# pi-kvm_v1_1.net
KiCad netlist of a schematic drawn in Altium Designer
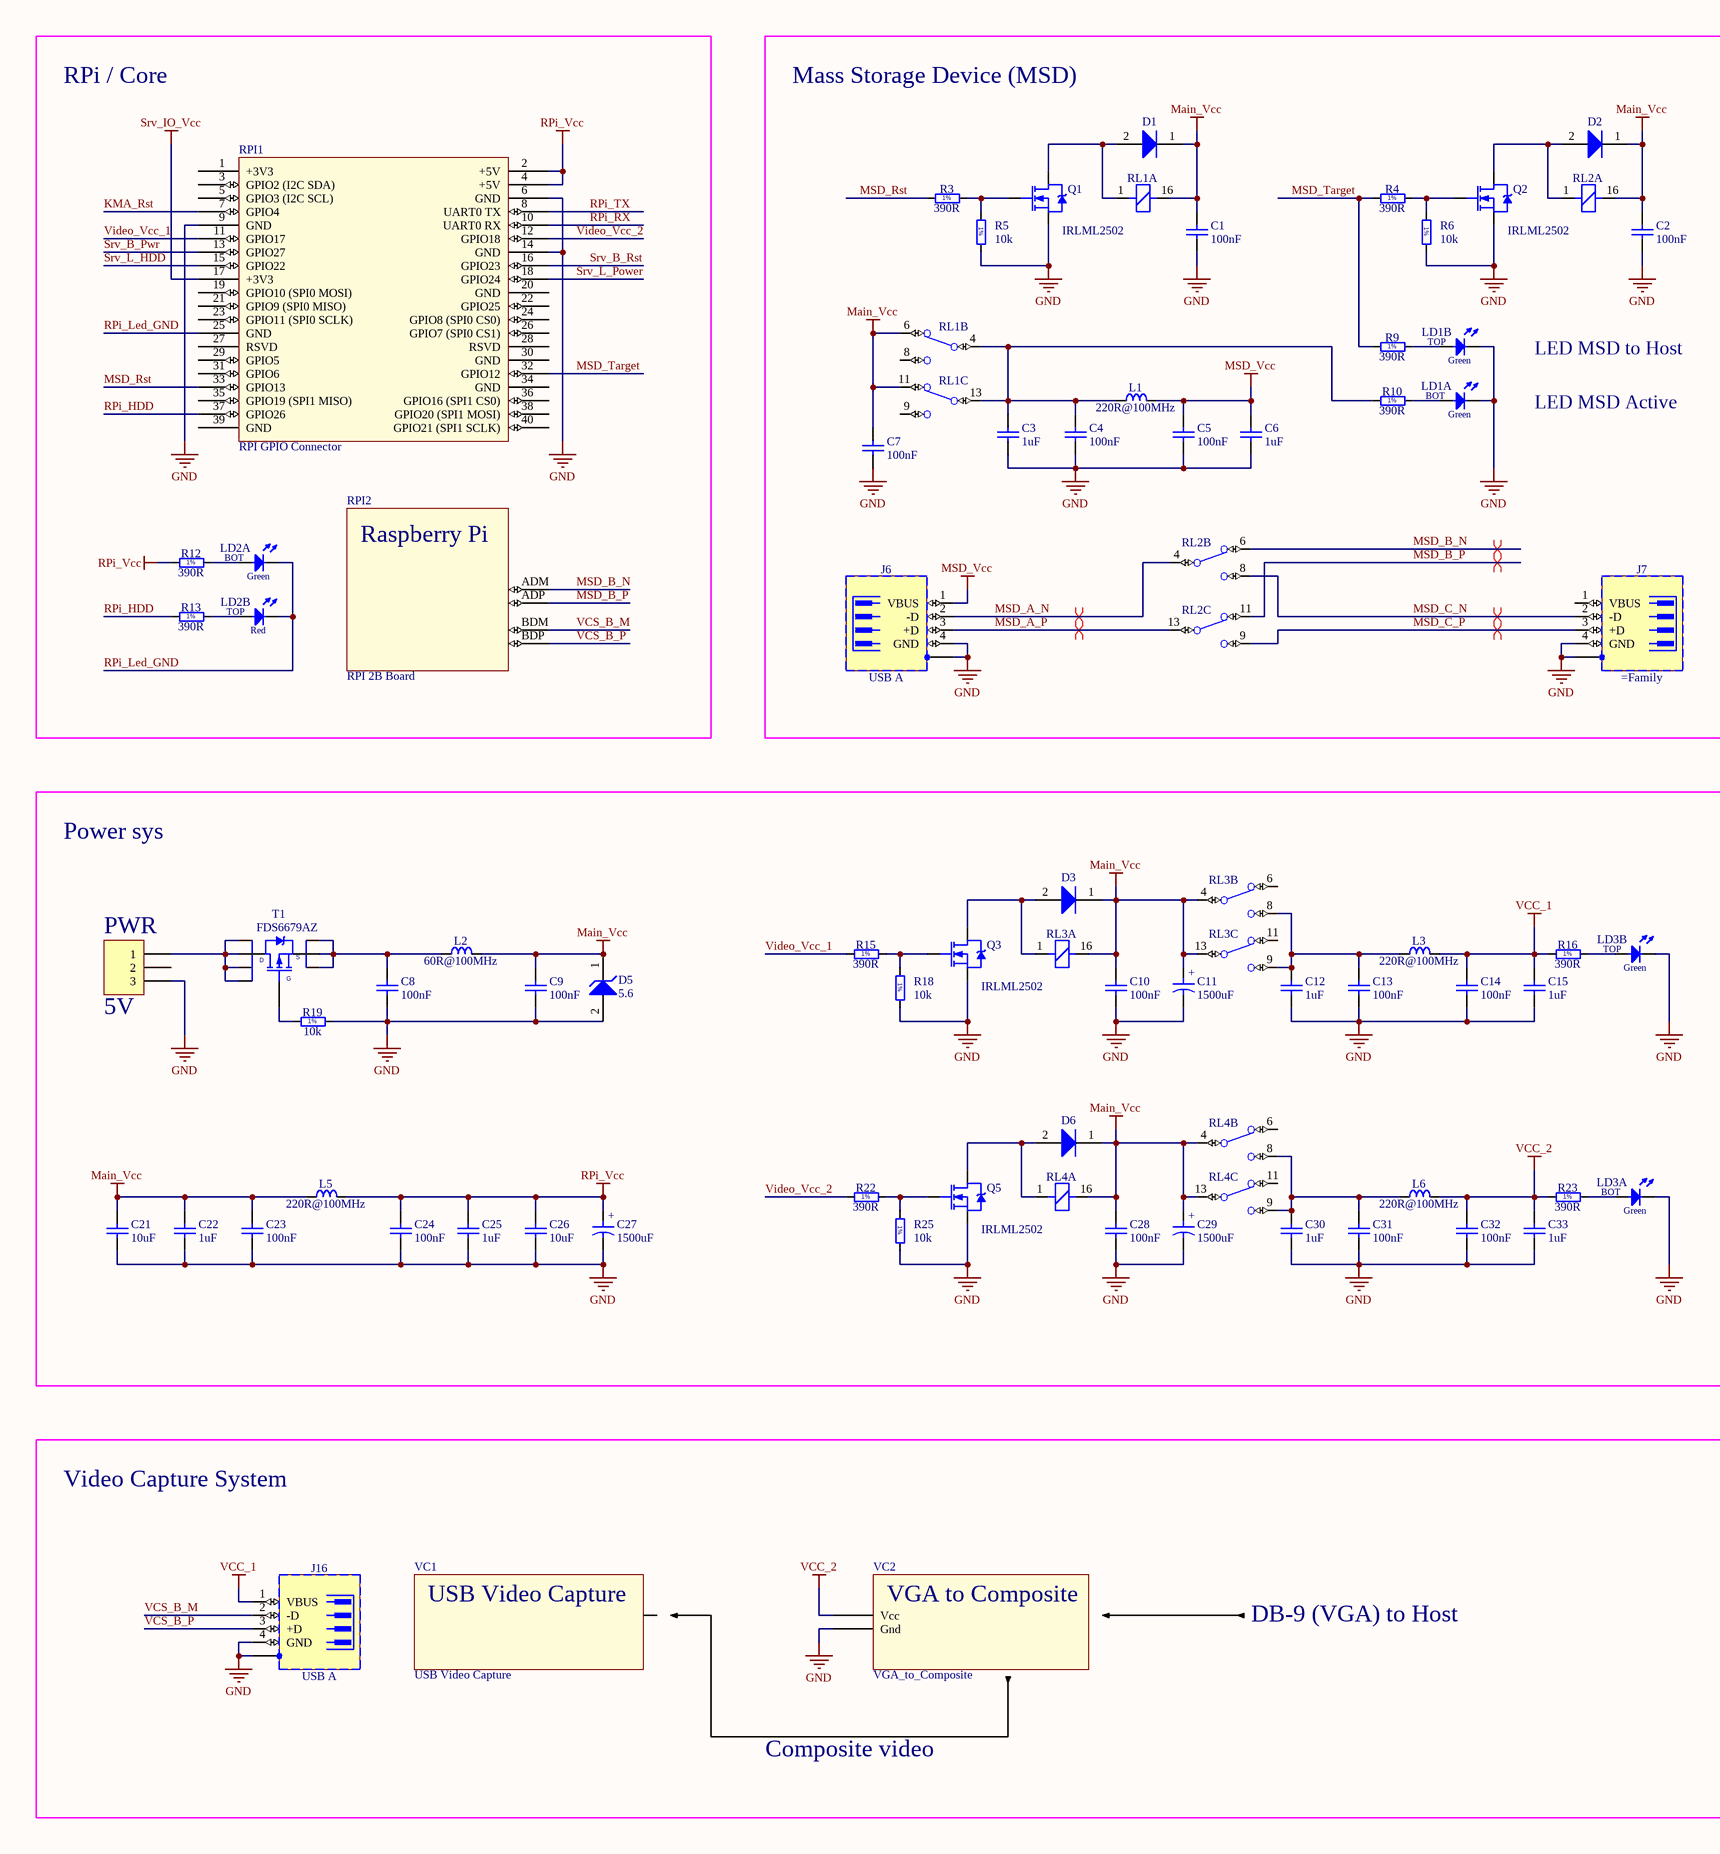
[diagram p0: pi-kvm_v1.1.SchDoc, left]
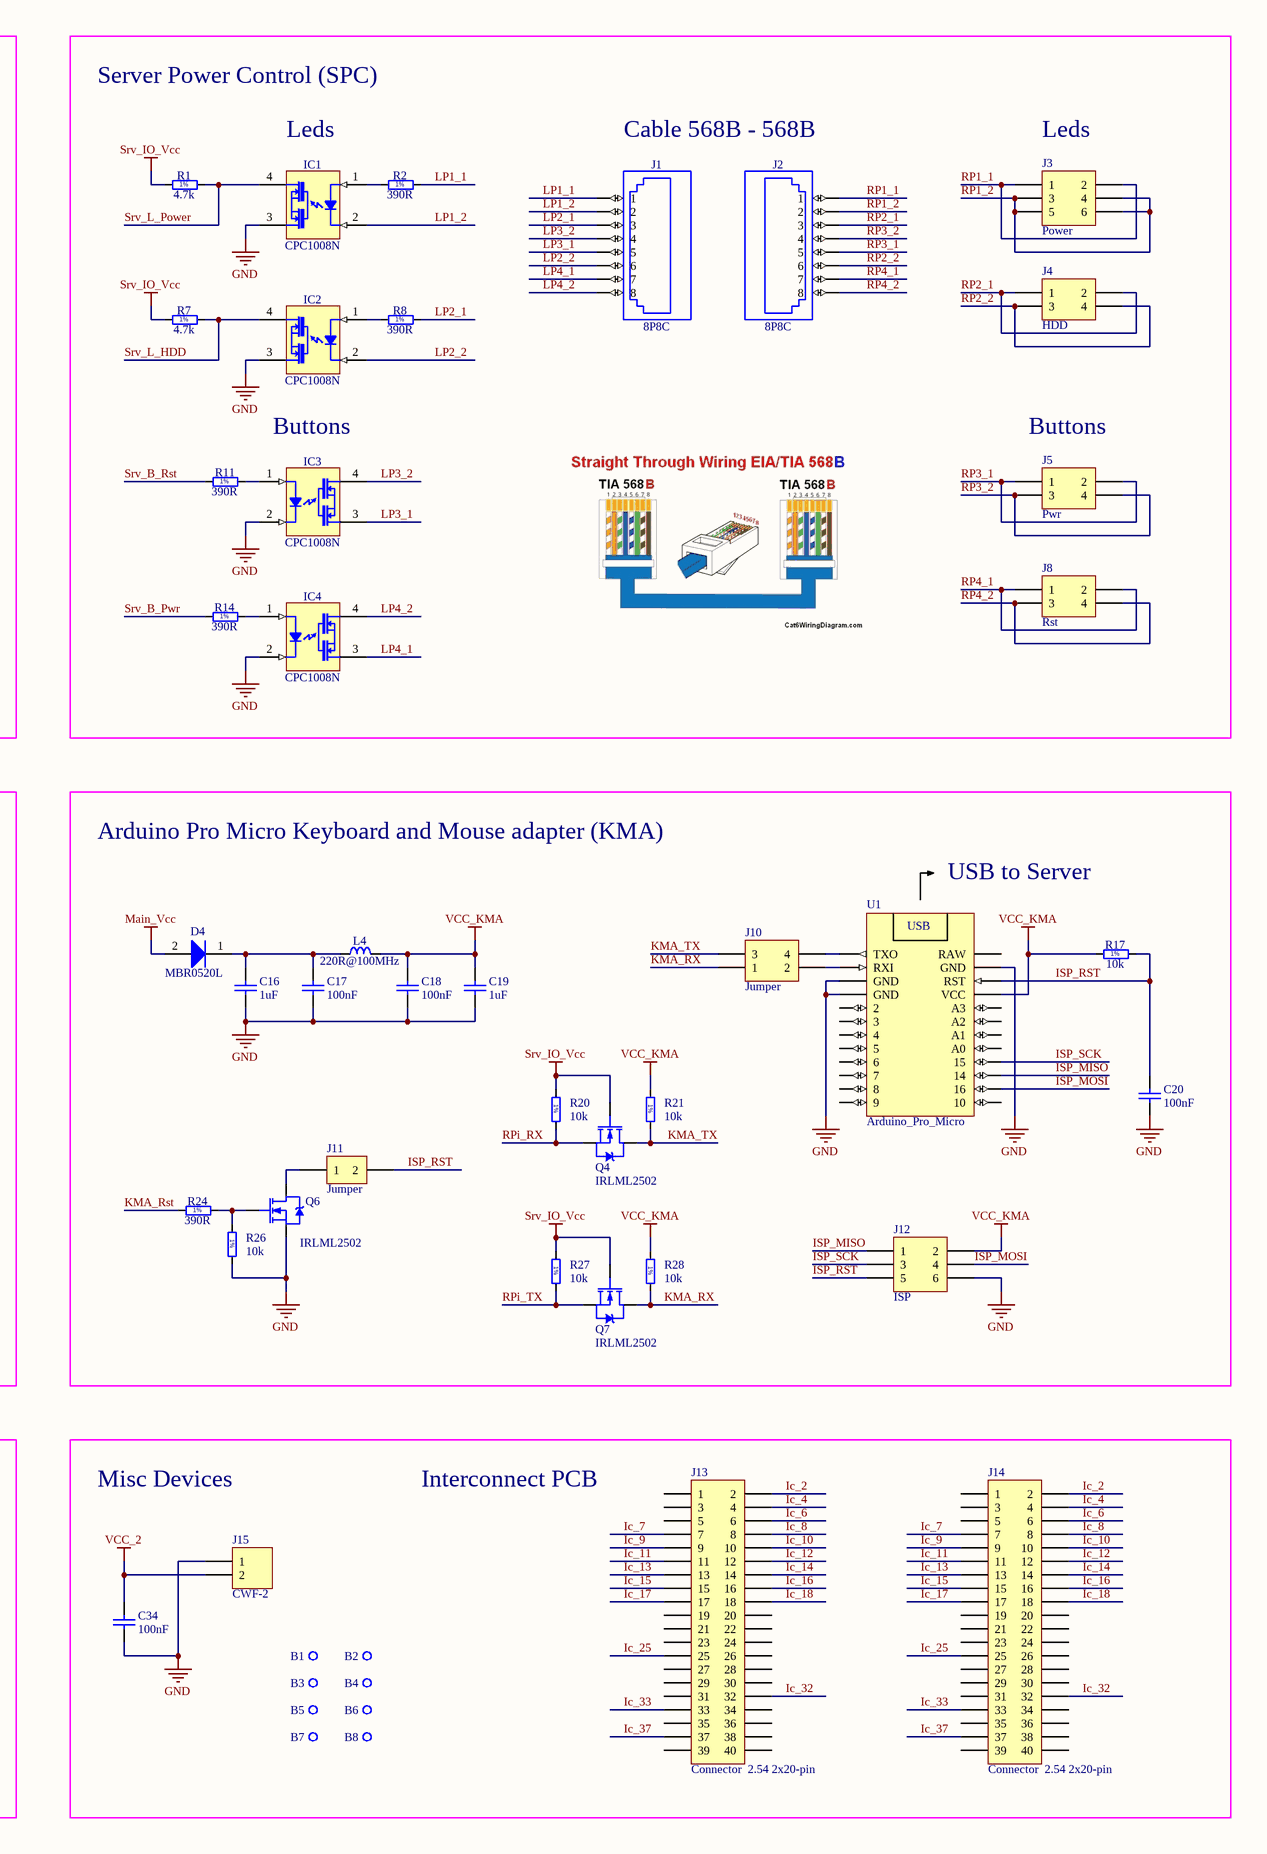
[diagram p1: pi-kvm_v1.1.SchDoc, right]

(export (version "E")
  (design (tool "Eeschema 10.0.6"))
  (components
    (comp (ref "B1")
      (value "~")
      (footprint "awesome_lib_1:MTG300_600_vias")
      (description "PLATED_HOLE3.0_PAD6.0")
      (fields (field (name "MANUFACTURER") "GENERIC"))
      (libsource (lib "awesome_lib_1") (part "PLATED_HOLE3.0_PAD6.0"))
    )
    (comp (ref "B2")
      (value "~")
      (footprint "awesome_lib_1:MTG300_600_vias")
      (description "PLATED_HOLE3.0_PAD6.0")
      (fields (field (name "MANUFACTURER") "GENERIC"))
      (libsource (lib "awesome_lib_1") (part "PLATED_HOLE3.0_PAD6.0"))
    )
    (comp (ref "B3")
      (value "~")
      (footprint "awesome_lib_1:MTG300_600_vias")
      (description "PLATED_HOLE3.0_PAD6.0")
      (fields (field (name "MANUFACTURER") "GENERIC"))
      (libsource (lib "awesome_lib_1") (part "PLATED_HOLE3.0_PAD6.0"))
    )
    (comp (ref "B4")
      (value "~")
      (footprint "awesome_lib_1:MTG300_600_vias")
      (description "PLATED_HOLE3.0_PAD6.0")
      (fields (field (name "MANUFACTURER") "GENERIC"))
      (libsource (lib "awesome_lib_1") (part "PLATED_HOLE3.0_PAD6.0"))
    )
    (comp (ref "B5")
      (value "~")
      (footprint "awesome_lib_1:MTG300_600_vias")
      (description "PLATED_HOLE3.0_PAD6.0")
      (fields (field (name "MANUFACTURER") "GENERIC"))
      (libsource (lib "awesome_lib_1") (part "PLATED_HOLE3.0_PAD6.0"))
    )
    (comp (ref "B6")
      (value "~")
      (footprint "awesome_lib_1:MTG300_600_vias")
      (description "PLATED_HOLE3.0_PAD6.0")
      (fields (field (name "MANUFACTURER") "GENERIC"))
      (libsource (lib "awesome_lib_1") (part "PLATED_HOLE3.0_PAD6.0"))
    )
    (comp (ref "B7")
      (value "~")
      (footprint "awesome_lib_1:MTG300_600_vias")
      (description "PLATED_HOLE3.0_PAD6.0")
      (fields (field (name "MANUFACTURER") "GENERIC"))
      (libsource (lib "awesome_lib_1") (part "PLATED_HOLE3.0_PAD6.0"))
    )
    (comp (ref "B8")
      (value "~")
      (footprint "awesome_lib_1:MTG300_600_vias")
      (description "PLATED_HOLE3.0_PAD6.0")
      (fields (field (name "MANUFACTURER") "GENERIC"))
      (libsource (lib "awesome_lib_1") (part "PLATED_HOLE3.0_PAD6.0"))
    )
    (comp (ref "C1")
      (value "100nF")
      (footprint "awesome_lib_1:CAPC2012X135N")
      (description "C_0805_100nF_50V_10%_X7R")
      (fields (field (name "VOLTAGE") "50V") (field (name "TOLERANCE") "10%"))
      (libsource (lib "awesome_lib_1") (part "C_0805_100nF_50V_10%_X7R"))
    )
    (comp (ref "C2")
      (value "100nF")
      (footprint "awesome_lib_1:CAPC2012X135N")
      (description "C_0805_100nF_50V_10%_X7R")
      (fields (field (name "VOLTAGE") "50V") (field (name "TOLERANCE") "10%"))
      (libsource (lib "awesome_lib_1") (part "C_0805_100nF_50V_10%_X7R"))
    )
    (comp (ref "C3")
      (value "1uF")
      (footprint "awesome_lib_1:CAPC2012X135N")
      (description "C_0805_1uF_16V_10%_X7R")
      (fields (field (name "VOLTAGE") "16V") (field (name "TOLERANCE") "10%"))
      (libsource (lib "awesome_lib_1") (part "C_0805_1uF_16V_10%_X7R"))
    )
    (comp (ref "C4")
      (value "100nF")
      (footprint "awesome_lib_1:CAPC2012X135N")
      (description "C_0805_100nF_50V_10%_X7R")
      (fields (field (name "VOLTAGE") "50V") (field (name "TOLERANCE") "10%"))
      (libsource (lib "awesome_lib_1") (part "C_0805_100nF_50V_10%_X7R"))
    )
    (comp (ref "C5")
      (value "100nF")
      (footprint "awesome_lib_1:CAPC2012X135N")
      (description "C_0805_100nF_50V_10%_X7R")
      (fields (field (name "VOLTAGE") "50V") (field (name "TOLERANCE") "10%"))
      (libsource (lib "awesome_lib_1") (part "C_0805_100nF_50V_10%_X7R"))
    )
    (comp (ref "C6")
      (value "1uF")
      (footprint "awesome_lib_1:CAPC2012X135N")
      (description "C_0805_1uF_16V_10%_X7R")
      (fields (field (name "VOLTAGE") "16V") (field (name "TOLERANCE") "10%"))
      (libsource (lib "awesome_lib_1") (part "C_0805_1uF_16V_10%_X7R"))
    )
    (comp (ref "C7")
      (value "100nF")
      (footprint "awesome_lib_1:CAPC2012X135N")
      (description "C_0805_100nF_50V_10%_X7R")
      (fields (field (name "VOLTAGE") "50V") (field (name "TOLERANCE") "10%"))
      (libsource (lib "awesome_lib_1") (part "C_0805_100nF_50V_10%_X7R"))
    )
    (comp (ref "C8")
      (value "100nF")
      (footprint "awesome_lib_1:CAPC2012X135N")
      (description "C_0805_100nF_50V_10%_X7R")
      (fields (field (name "VOLTAGE") "50V") (field (name "TOLERANCE") "10%"))
      (libsource (lib "awesome_lib_1") (part "C_0805_100nF_50V_10%_X7R"))
    )
    (comp (ref "C9")
      (value "100nF")
      (footprint "awesome_lib_1:CAPC2012X135N")
      (description "C_0805_100nF_50V_10%_X7R")
      (fields (field (name "VOLTAGE") "50V") (field (name "TOLERANCE") "10%"))
      (libsource (lib "awesome_lib_1") (part "C_0805_100nF_50V_10%_X7R"))
    )
    (comp (ref "C10")
      (value "100nF")
      (footprint "awesome_lib_1:CAPC2012X135N")
      (description "C_0805_100nF_50V_10%_X7R")
      (fields (field (name "VOLTAGE") "50V") (field (name "TOLERANCE") "10%"))
      (libsource (lib "awesome_lib_1") (part "C_0805_100nF_50V_10%_X7R"))
    )
    (comp (ref "C11")
      (value "1500uF")
      (footprint "awesome_lib_1:CAPPR500-1050X1300")
      (description "Cap 1500uF x 6.3V")
      (fields (field (name "VOLTAGE") "6.3V") (field (name "TOLERANCE") "±20%"))
      (libsource (lib "awesome_lib_1") (part "Cap 1500uF x 6.3V"))
    )
    (comp (ref "C12")
      (value "1uF")
      (footprint "awesome_lib_1:CAPC2012X135N")
      (description "C_0805_1uF_16V_10%_X7R")
      (fields (field (name "VOLTAGE") "16V") (field (name "TOLERANCE") "10%"))
      (libsource (lib "awesome_lib_1") (part "C_0805_1uF_16V_10%_X7R"))
    )
    (comp (ref "C13")
      (value "100nF")
      (footprint "awesome_lib_1:CAPC2012X135N")
      (description "C_0805_100nF_50V_10%_X7R")
      (fields (field (name "VOLTAGE") "50V") (field (name "TOLERANCE") "10%"))
      (libsource (lib "awesome_lib_1") (part "C_0805_100nF_50V_10%_X7R"))
    )
    (comp (ref "C14")
      (value "100nF")
      (footprint "awesome_lib_1:CAPC2012X135N")
      (description "C_0805_100nF_50V_10%_X7R")
      (fields (field (name "VOLTAGE") "50V") (field (name "TOLERANCE") "10%"))
      (libsource (lib "awesome_lib_1") (part "C_0805_100nF_50V_10%_X7R"))
    )
    (comp (ref "C15")
      (value "1uF")
      (footprint "awesome_lib_1:CAPC2012X135N")
      (description "C_0805_1uF_16V_10%_X7R")
      (fields (field (name "VOLTAGE") "16V") (field (name "TOLERANCE") "10%"))
      (libsource (lib "awesome_lib_1") (part "C_0805_1uF_16V_10%_X7R"))
    )
    (comp (ref "C16")
      (value "1uF")
      (footprint "awesome_lib_1:CAPC2012X135N")
      (description "C_0805_1uF_16V_10%_X7R")
      (fields (field (name "VOLTAGE") "16V") (field (name "TOLERANCE") "10%"))
      (libsource (lib "awesome_lib_1") (part "C_0805_1uF_16V_10%_X7R"))
    )
    (comp (ref "C17")
      (value "100nF")
      (footprint "awesome_lib_1:CAPC2012X135N")
      (description "C_0805_100nF_50V_10%_X7R")
      (fields (field (name "VOLTAGE") "50V") (field (name "TOLERANCE") "10%"))
      (libsource (lib "awesome_lib_1") (part "C_0805_100nF_50V_10%_X7R"))
    )
    (comp (ref "C18")
      (value "100nF")
      (footprint "awesome_lib_1:CAPC2012X135N")
      (description "C_0805_100nF_50V_10%_X7R")
      (fields (field (name "VOLTAGE") "50V") (field (name "TOLERANCE") "10%"))
      (libsource (lib "awesome_lib_1") (part "C_0805_100nF_50V_10%_X7R"))
    )
    (comp (ref "C19")
      (value "1uF")
      (footprint "awesome_lib_1:CAPC2012X135N")
      (description "C_0805_1uF_16V_10%_X7R")
      (fields (field (name "VOLTAGE") "16V") (field (name "TOLERANCE") "10%"))
      (libsource (lib "awesome_lib_1") (part "C_0805_1uF_16V_10%_X7R"))
    )
    (comp (ref "C20")
      (value "100nF")
      (footprint "awesome_lib_1:CAPC2012X135N")
      (description "C_0805_100nF_50V_10%_X7R")
      (fields (field (name "VOLTAGE") "50V") (field (name "TOLERANCE") "10%"))
      (libsource (lib "awesome_lib_1") (part "C_0805_100nF_50V_10%_X7R"))
    )
    (comp (ref "C21")
      (value "10uF")
      (footprint "awesome_lib_1:CAPC2012X135N")
      (description "C_0805_10uF_10V_10%_X7R")
      (fields (field (name "VOLTAGE") "10V") (field (name "TOLERANCE") "10%"))
      (libsource (lib "awesome_lib_1") (part "C_0805_10uF_10V_10%_X7R"))
    )
    (comp (ref "C22")
      (value "1uF")
      (footprint "awesome_lib_1:CAPC2012X135N")
      (description "C_0805_1uF_16V_10%_X7R")
      (fields (field (name "VOLTAGE") "16V") (field (name "TOLERANCE") "10%"))
      (libsource (lib "awesome_lib_1") (part "C_0805_1uF_16V_10%_X7R"))
    )
    (comp (ref "C23")
      (value "100nF")
      (footprint "awesome_lib_1:CAPC2012X135N")
      (description "C_0805_100nF_50V_10%_X7R")
      (fields (field (name "VOLTAGE") "50V") (field (name "TOLERANCE") "10%"))
      (libsource (lib "awesome_lib_1") (part "C_0805_100nF_50V_10%_X7R"))
    )
    (comp (ref "C24")
      (value "100nF")
      (footprint "awesome_lib_1:CAPC2012X135N")
      (description "C_0805_100nF_50V_10%_X7R")
      (fields (field (name "VOLTAGE") "50V") (field (name "TOLERANCE") "10%"))
      (libsource (lib "awesome_lib_1") (part "C_0805_100nF_50V_10%_X7R"))
    )
    (comp (ref "C25")
      (value "1uF")
      (footprint "awesome_lib_1:CAPC2012X135N")
      (description "C_0805_1uF_16V_10%_X7R")
      (fields (field (name "VOLTAGE") "16V") (field (name "TOLERANCE") "10%"))
      (libsource (lib "awesome_lib_1") (part "C_0805_1uF_16V_10%_X7R"))
    )
    (comp (ref "C26")
      (value "10uF")
      (footprint "awesome_lib_1:CAPC2012X135N")
      (description "C_0805_10uF_10V_10%_X7R")
      (fields (field (name "VOLTAGE") "10V") (field (name "TOLERANCE") "10%"))
      (libsource (lib "awesome_lib_1") (part "C_0805_10uF_10V_10%_X7R"))
    )
    (comp (ref "C27")
      (value "1500uF")
      (footprint "awesome_lib_1:CAPPR500-1050X1300")
      (description "Cap 1500uF x 6.3V")
      (fields (field (name "VOLTAGE") "6.3V") (field (name "TOLERANCE") "±20%"))
      (libsource (lib "awesome_lib_1") (part "Cap 1500uF x 6.3V"))
    )
    (comp (ref "C28")
      (value "100nF")
      (footprint "awesome_lib_1:CAPC2012X135N")
      (description "C_0805_100nF_50V_10%_X7R")
      (fields (field (name "VOLTAGE") "50V") (field (name "TOLERANCE") "10%"))
      (libsource (lib "awesome_lib_1") (part "C_0805_100nF_50V_10%_X7R"))
    )
    (comp (ref "C29")
      (value "1500uF")
      (footprint "awesome_lib_1:CAPPR500-1050X1300")
      (description "Cap 1500uF x 6.3V")
      (fields (field (name "VOLTAGE") "6.3V") (field (name "TOLERANCE") "±20%"))
      (libsource (lib "awesome_lib_1") (part "Cap 1500uF x 6.3V"))
    )
    (comp (ref "C30")
      (value "1uF")
      (footprint "awesome_lib_1:CAPC2012X135N")
      (description "C_0805_1uF_16V_10%_X7R")
      (fields (field (name "VOLTAGE") "16V") (field (name "TOLERANCE") "10%"))
      (libsource (lib "awesome_lib_1") (part "C_0805_1uF_16V_10%_X7R"))
    )
    (comp (ref "C31")
      (value "100nF")
      (footprint "awesome_lib_1:CAPC2012X135N")
      (description "C_0805_100nF_50V_10%_X7R")
      (fields (field (name "VOLTAGE") "50V") (field (name "TOLERANCE") "10%"))
      (libsource (lib "awesome_lib_1") (part "C_0805_100nF_50V_10%_X7R"))
    )
    (comp (ref "C32")
      (value "100nF")
      (footprint "awesome_lib_1:CAPC2012X135N")
      (description "C_0805_100nF_50V_10%_X7R")
      (fields (field (name "VOLTAGE") "50V") (field (name "TOLERANCE") "10%"))
      (libsource (lib "awesome_lib_1") (part "C_0805_100nF_50V_10%_X7R"))
    )
    (comp (ref "C33")
      (value "1uF")
      (footprint "awesome_lib_1:CAPC2012X135N")
      (description "C_0805_1uF_16V_10%_X7R")
      (fields (field (name "VOLTAGE") "16V") (field (name "TOLERANCE") "10%"))
      (libsource (lib "awesome_lib_1") (part "C_0805_1uF_16V_10%_X7R"))
    )
    (comp (ref "C34")
      (value "100nF")
      (footprint "awesome_lib_1:CAPC2012X135N")
      (description "C_0805_100nF_50V_10%_X7R")
      (fields (field (name "VOLTAGE") "50V") (field (name "TOLERANCE") "10%"))
      (libsource (lib "awesome_lib_1") (part "C_0805_100nF_50V_10%_X7R"))
    )
    (comp (ref "D1")
      (value "1N4148W")
      (footprint "awesome_lib_1:SOD3816X118N")
      (fields (field (name "MANUFACTURER") "On Semiconductor(ONS)"))
      (libsource (lib "awesome_lib_1") (part "1N4148W"))
    )
    (comp (ref "D2")
      (value "1N4148W")
      (footprint "awesome_lib_1:SOD3816X118N")
      (fields (field (name "MANUFACTURER") "On Semiconductor(ONS)"))
      (libsource (lib "awesome_lib_1") (part "1N4148W"))
    )
    (comp (ref "D3")
      (value "1N4148W")
      (footprint "awesome_lib_1:SOD3816X118N")
      (fields (field (name "MANUFACTURER") "On Semiconductor(ONS)"))
      (libsource (lib "awesome_lib_1") (part "1N4148W"))
    )
    (comp (ref "D4")
      (value "MBR0520L")
      (footprint "awesome_lib_1:SOD3816X118N")
      (fields (field (name "MANUFACTURER") "On Semiconductor(ONS)"))
      (libsource (lib "awesome_lib_1") (part "MBR0520L"))
    )
    (comp (ref "D5")
      (value "5.6")
      (footprint "awesome_lib_1:DIOM5027X244N")
      (description "1.5 W Zener Voltage Regulator, 2-Pin SMA, Pb-Free, Tape and Reel")
      (fields
        (field (name "MANUFACTURER") "On Semiconductor")
        (field (name "MANUFACTURER PART NUMBER") "1SMA5919BT3G")
      )
      (libsource (lib "awesome_lib_1") (part "1SMA5919BT3G"))
    )
    (comp (ref "D6")
      (value "1N4148W")
      (footprint "awesome_lib_1:SOD3816X118N")
      (fields (field (name "MANUFACTURER") "On Semiconductor(ONS)"))
      (libsource (lib "awesome_lib_1") (part "1N4148W"))
    )
    (comp (ref "IC1")
      (value "CPC1008N")
      (footprint "awesome_lib_1:SOIC254P610X218-4N")
      (description "PhotoMOS Relay")
      (fields (field (name "MANUFACTURER") "Ixys Corporation (IXYS)"))
      (libsource (lib "awesome_lib_1") (part "PhotoMOS Relay x1 Type2"))
    )
    (comp (ref "IC2")
      (value "CPC1008N")
      (footprint "awesome_lib_1:SOIC254P610X218-4N")
      (description "PhotoMOS Relay")
      (fields (field (name "MANUFACTURER") "Ixys Corporation (IXYS)"))
      (libsource (lib "awesome_lib_1") (part "PhotoMOS Relay x1 Type2"))
    )
    (comp (ref "IC3")
      (value "CPC1008N")
      (footprint "awesome_lib_1:SOIC254P610X218-4N")
      (description "PhotoMOS Relay")
      (fields (field (name "MANUFACTURER") "Ixys Corporation (IXYS)"))
      (libsource (lib "") (part "PhotoMOS Relay x1 Type2_1"))
    )
    (comp (ref "IC4")
      (value "CPC1008N")
      (footprint "awesome_lib_1:SOIC254P610X218-4N")
      (description "PhotoMOS Relay")
      (fields (field (name "MANUFACTURER") "Ixys Corporation (IXYS)"))
      (libsource (lib "") (part "PhotoMOS Relay x1 Type2_1"))
    )
    (comp (ref "J1")
      (value "8P8C")
      (footprint "awesome_lib_1:FCI_54602-908LF")
      (description "1 Port, 8 Positions, CAT3 RJ45 Horizontal Modular Jack")
      (fields
        (field (name "MANUFACTURER") "Fci Electronics(FCI)")
        (field (name "MANUFACTURER PART NUMBER") "54602-908LF")
      )
      (libsource (lib "awesome_lib_1") (part "FCI_54602-908LF"))
    )
    (comp (ref "J2")
      (value "8P8C")
      (footprint "awesome_lib_1:FCI_54602-908LF")
      (description "1 Port, 8 Positions, CAT3 RJ45 Horizontal Modular Jack")
      (fields
        (field (name "MANUFACTURER") "Fci Electronics(FCI)")
        (field (name "MANUFACTURER PART NUMBER") "54602-908LF")
      )
      (libsource (lib "awesome_lib_1") (part "FCI_54602-908LF"))
    )
    (comp (ref "J3")
      (value "Power")
      (footprint "awesome_lib_1:SAMTEC_MTLW-103-07-L-D-250")
      (description "Connector  2.54 3x2-pin")
      (fields
        (field (name "MANUFACTURER") "CONNFLY ELECTRONIC CO.,LTD.(CONNFLY)")
        (field (name "MANUFACTURER PART NUMBER") "PLD-6")
      )
      (libsource (lib "awesome_lib_1") (part "Connector  2.54 3x2-pin"))
    )
    (comp (ref "J4")
      (value "HDD")
      (footprint "awesome_lib_1:SAMTEC_MTLW-102-07-L-D-250")
      (description "Connector  2.54 2x2-pin")
      (fields
        (field (name "MANUFACTURER") "CONNFLY ELECTRONIC CO.,LTD.(CONNFLY)")
        (field (name "MANUFACTURER PART NUMBER") "PLD-8")
      )
      (libsource (lib "awesome_lib_1") (part "Connector  2.54 2x2-pin"))
    )
    (comp (ref "J5")
      (value "Pwr")
      (footprint "awesome_lib_1:SAMTEC_MTLW-102-07-L-D-250")
      (description "Connector  2.54 2x2-pin")
      (fields
        (field (name "MANUFACTURER") "CONNFLY ELECTRONIC CO.,LTD.(CONNFLY)")
        (field (name "MANUFACTURER PART NUMBER") "PLD-8")
      )
      (libsource (lib "awesome_lib_1") (part "Connector  2.54 2x2-pin"))
    )
    (comp (ref "J6")
      (value "USB A")
      (footprint "awesome_lib_1:FCI_87520-0010BLF")
      (description "4 Pin + 1 Shield USB Receptacle")
      (fields
        (field (name "MANUFACTURER") "Te Connectivity(TE)")
        (field (name "MANUFACTURER PART NUMBER") "292303-1")
      )
      (libsource (lib "") (part "Connector USB A - 4 Pin + 1Shield_1"))
    )
    (comp (ref "J7")
      (value "~")
      (footprint "awesome_lib_1:TYCO_292304-1")
      (description "4 Pin + 1 Shield USB Receptacle")
      (fields
        (field (name "MANUFACTURER") "Te Connectivity(TE)")
        (field (name "MANUFACTURER PART NUMBER") "292304-1")
      )
      (libsource (lib "awesome_lib_1") (part "Connector USB B - 4 Pin + 1Shield"))
    )
    (comp (ref "J8")
      (value "Rst")
      (footprint "awesome_lib_1:SAMTEC_MTLW-102-07-L-D-250")
      (description "Connector  2.54 2x2-pin")
      (fields
        (field (name "MANUFACTURER") "CONNFLY ELECTRONIC CO.,LTD.(CONNFLY)")
        (field (name "MANUFACTURER PART NUMBER") "PLD-8")
      )
      (libsource (lib "awesome_lib_1") (part "Connector  2.54 2x2-pin"))
    )
    (comp (ref "J9")
      (value "Connector  5.08 3-pin")
      (footprint "awesome_lib_1:PHOENIX_1755749")
      (libsource (lib "awesome_lib_1") (part "Connector  5.08 3-pin"))
    )
    (comp (ref "J10")
      (value "Jumper")
      (footprint "awesome_lib_1:SAMTEC_MTLW-102-07-L-D-250")
      (description "Connector  2.54 2x2-pin")
      (fields
        (field (name "MANUFACTURER") "CONNFLY ELECTRONIC CO.,LTD.(CONNFLY)")
        (field (name "MANUFACTURER PART NUMBER") "PLD-8")
      )
      (libsource (lib "") (part "Connector  2.54 2x2-pin_1"))
    )
    (comp (ref "J11")
      (value "Jumper")
      (footprint "awesome_lib_1:COMATEL_385.0358.1.02.400")
      (description "Connector  2.54 2-pin")
      (fields
        (field (name "MANUFACTURER PART NUMBER") "PLS-2")
        (field (name "MANUFACTURER") "CONNFLY ELECTRONIC CO.,LTD.(CONNFLY)")
      )
      (libsource (lib "awesome_lib_1") (part "Connector  2.54 2-pin opposite"))
    )
    (comp (ref "J12")
      (value "ISP")
      (footprint "awesome_lib_1:SAMTEC_MTLW-103-07-L-D-250")
      (description "Connector  2.54 3x2-pin")
      (fields
        (field (name "MANUFACTURER") "CONNFLY ELECTRONIC CO.,LTD.(CONNFLY)")
        (field (name "MANUFACTURER PART NUMBER") "PLD-6")
      )
      (libsource (lib "awesome_lib_1") (part "Connector  2.54 3x2-pin"))
    )
    (comp (ref "J13")
      (value "Connector  2.54 2x20-pin")
      (footprint "awesome_lib_1:FCI_87606-320LF")
      (fields
        (field (name "MANUFACTURER") "CONNFLY ELECTRONIC CO.,LTD.(CONNFLY)")
        (field (name "MANUFACTURER PART NUMBER") "PBD-40")
      )
      (libsource (lib "awesome_lib_1") (part "Connector  2.54 2x20-pin"))
    )
    (comp (ref "J14")
      (value "Connector  2.54 2x20-pin")
      (footprint "awesome_lib_1:FCI_87606-320LF")
      (fields
        (field (name "MANUFACTURER") "CONNFLY ELECTRONIC CO.,LTD.(CONNFLY)")
        (field (name "MANUFACTURER PART NUMBER") "PBD-40")
      )
      (libsource (lib "awesome_lib_1") (part "Connector  2.54 2x20-pin"))
    )
    (comp (ref "J15")
      (value "CWF-2")
      (footprint "awesome_lib_1:CWF-2")
      (fields
        (field (name "MANUFACTURER PART NUMBER") "DS1069-2 M (CWF-2)")
        (field (name "MANUFACTURER") "CONNFLY ELECTRONIC CO.,LTD.(CONNFLY)")
      )
      (libsource (lib "awesome_lib_1") (part "CWF-2"))
    )
    (comp (ref "J16")
      (value "USB A")
      (footprint "awesome_lib_1:FCI_87520-0010BLF")
      (description "4 Pin + 1 Shield USB Receptacle")
      (fields
        (field (name "MANUFACTURER") "Te Connectivity(TE)")
        (field (name "MANUFACTURER PART NUMBER") "292303-1")
      )
      (libsource (lib "awesome_lib_1") (part "Connector USB A - 4 Pin + 1Shield"))
    )
    (comp (ref "L1")
      (value "220R@100MHz")
      (footprint "awesome_lib_1:INDC2012X105N")
      (description "BLM21PG221SN1D")
      (fields (field (name "TOLERANCE") "±25%") (field (name "MANUFACTURER") "Murata Electronics Inc. (MUR)"))
      (libsource (lib "awesome_lib_1") (part "BLM21PG221SN1D"))
    )
    (comp (ref "L2")
      (value "60R@100MHz")
      (footprint "awesome_lib_1:INDC4516X180N")
      (description "BLM41PG600SN1L")
      (fields (field (name "MANUFACTURER") "Murata Electronics Inc. (MUR)"))
      (libsource (lib "awesome_lib_1") (part "BLM41PG600SN1L"))
    )
    (comp (ref "L3")
      (value "220R@100MHz")
      (footprint "awesome_lib_1:INDC2012X105N")
      (description "BLM21PG221SN1D")
      (fields (field (name "TOLERANCE") "±25%") (field (name "MANUFACTURER") "Murata Electronics Inc. (MUR)"))
      (libsource (lib "awesome_lib_1") (part "BLM21PG221SN1D"))
    )
    (comp (ref "L4")
      (value "220R@100MHz")
      (footprint "awesome_lib_1:INDC2012X105N")
      (description "BLM21PG221SN1D")
      (fields (field (name "TOLERANCE") "±25%") (field (name "MANUFACTURER") "Murata Electronics Inc. (MUR)"))
      (libsource (lib "awesome_lib_1") (part "BLM21PG221SN1D"))
    )
    (comp (ref "L5")
      (value "220R@100MHz")
      (footprint "awesome_lib_1:INDC2012X105N")
      (description "BLM21PG221SN1D")
      (fields (field (name "TOLERANCE") "±25%") (field (name "MANUFACTURER") "Murata Electronics Inc. (MUR)"))
      (libsource (lib "awesome_lib_1") (part "BLM21PG221SN1D"))
    )
    (comp (ref "L6")
      (value "220R@100MHz")
      (footprint "awesome_lib_1:INDC2012X105N")
      (description "BLM21PG221SN1D")
      (fields (field (name "TOLERANCE") "±25%") (field (name "MANUFACTURER") "Murata Electronics Inc. (MUR)"))
      (libsource (lib "awesome_lib_1") (part "BLM21PG221SN1D"))
    )
    (comp (ref "LD1")
      (value "~")
      (footprint "awesome_lib_1:LED_DIALIGHT_553-0122-200F")
      (description "LED x2 Green 1C2A-BOT_3C4A-TOP")
      (fields
        (field (name "MANUFACTURER") "Dialight Corp.(DIALIGHT)")
        (field (name "MANUFACTURER PART NUMBER") "553-0122-200F")
      )
      (libsource (lib "awesome_lib_1") (part "LED x2 Green 1C2A-BOT_3C4A-TOP"))
    )
    (comp (ref "LD2")
      (value "~")
      (footprint "awesome_lib_1:LED_DIALIGHT_553-0112-200F")
      (description "2x LED  Botom Green, Top Red")
      (fields
        (field (name "MANUFACTURER") "Dialight Corp.(DIALIGHT)")
        (field (name "MANUFACTURER PART NUMBER") "553-0112-200F")
      )
      (libsource (lib "awesome_lib_1") (part "LED x2 G-1C2A-BOT_R-3C4A-TOP"))
    )
    (comp (ref "LD3")
      (value "~")
      (footprint "awesome_lib_1:LED_DIALIGHT_553-0122-200F")
      (description "LED x2 Green 1C2A-BOT_3C4A-TOP")
      (fields
        (field (name "MANUFACTURER") "Dialight Corp.(DIALIGHT)")
        (field (name "MANUFACTURER PART NUMBER") "553-0122-200F")
      )
      (libsource (lib "awesome_lib_1") (part "LED x2 Green 1C2A-BOT_3C4A-TOP"))
    )
    (comp (ref "Q1")
      (value "IRLML2502")
      (footprint "awesome_lib_1:SOT23")
      (description "N-ch 20V 4.2A 45mOhm")
      (fields
        (field (name "MANUFACTURER") "Infineon Technologies Ag (Siemens Semiconductors) (INFIN)")
        (field (name "MANUFACTURER PART NUMBER") "IRLML2502GTRPBF")
      )
      (libsource (lib "awesome_lib_1") (part "IRLML2502"))
    )
    (comp (ref "Q2")
      (value "IRLML2502")
      (footprint "awesome_lib_1:SOT23")
      (description "N-ch 20V 4.2A 45mOhm")
      (fields
        (field (name "MANUFACTURER") "Infineon Technologies Ag (Siemens Semiconductors) (INFIN)")
        (field (name "MANUFACTURER PART NUMBER") "IRLML2502GTRPBF")
      )
      (libsource (lib "awesome_lib_1") (part "IRLML2502"))
    )
    (comp (ref "Q3")
      (value "IRLML2502")
      (footprint "awesome_lib_1:SOT23")
      (description "N-ch 20V 4.2A 45mOhm")
      (fields
        (field (name "MANUFACTURER") "Infineon Technologies Ag (Siemens Semiconductors) (INFIN)")
        (field (name "MANUFACTURER PART NUMBER") "IRLML2502GTRPBF")
      )
      (libsource (lib "awesome_lib_1") (part "IRLML2502"))
    )
    (comp (ref "Q4")
      (value "IRLML2502")
      (footprint "awesome_lib_1:SOT23")
      (description "N-ch 20V 4.2A 45mOhm")
      (fields
        (field (name "MANUFACTURER") "Infineon Technologies Ag (Siemens Semiconductors) (INFIN)")
        (field (name "MANUFACTURER PART NUMBER") "IRLML2502GTRPBF")
      )
      (libsource (lib "awesome_lib_1") (part "IRLML2502"))
    )
    (comp (ref "Q5")
      (value "IRLML2502")
      (footprint "awesome_lib_1:SOT23")
      (description "N-ch 20V 4.2A 45mOhm")
      (fields
        (field (name "MANUFACTURER") "Infineon Technologies Ag (Siemens Semiconductors) (INFIN)")
        (field (name "MANUFACTURER PART NUMBER") "IRLML2502GTRPBF")
      )
      (libsource (lib "awesome_lib_1") (part "IRLML2502"))
    )
    (comp (ref "Q6")
      (value "IRLML2502")
      (footprint "awesome_lib_1:SOT23")
      (description "N-ch 20V 4.2A 45mOhm")
      (fields
        (field (name "MANUFACTURER") "Infineon Technologies Ag (Siemens Semiconductors) (INFIN)")
        (field (name "MANUFACTURER PART NUMBER") "IRLML2502GTRPBF")
      )
      (libsource (lib "awesome_lib_1") (part "IRLML2502"))
    )
    (comp (ref "Q7")
      (value "IRLML2502")
      (footprint "awesome_lib_1:SOT23")
      (description "N-ch 20V 4.2A 45mOhm")
      (fields
        (field (name "MANUFACTURER") "Infineon Technologies Ag (Siemens Semiconductors) (INFIN)")
        (field (name "MANUFACTURER PART NUMBER") "IRLML2502GTRPBF")
      )
      (libsource (lib "awesome_lib_1") (part "IRLML2502"))
    )
    (comp (ref "R1")
      (value "4.7k")
      (footprint "awesome_lib_1:RESC2012X60N")
      (description "R_0805_4.7k_150V_125mW_1%")
      (fields (field (name "POWER") "125mW") (field (name "TOLERANCE") "1%"))
      (libsource (lib "awesome_lib_1") (part "R_0805_4.7k_150V_125mW_1%"))
    )
    (comp (ref "R2")
      (value "390R")
      (footprint "awesome_lib_1:RESC2012X60N")
      (description "R_0805_390R_150V_125mW_1%")
      (fields (field (name "POWER") "125mW") (field (name "TOLERANCE") "1%"))
      (libsource (lib "awesome_lib_1") (part "R_0805_390R_150V_125mW_1%"))
    )
    (comp (ref "R3")
      (value "390R")
      (footprint "awesome_lib_1:RESC2012X60N")
      (description "R_0805_390R_150V_125mW_1%")
      (fields (field (name "POWER") "125mW") (field (name "TOLERANCE") "1%"))
      (libsource (lib "awesome_lib_1") (part "R_0805_390R_150V_125mW_1%"))
    )
    (comp (ref "R4")
      (value "390R")
      (footprint "awesome_lib_1:RESC2012X60N")
      (description "R_0805_390R_150V_125mW_1%")
      (fields (field (name "POWER") "125mW") (field (name "TOLERANCE") "1%"))
      (libsource (lib "awesome_lib_1") (part "R_0805_390R_150V_125mW_1%"))
    )
    (comp (ref "R5")
      (value "10k")
      (footprint "awesome_lib_1:RESC2012X60N")
      (description "R_0805_10k_150V_125mW_1%")
      (fields (field (name "POWER") "125mW") (field (name "TOLERANCE") "1%"))
      (libsource (lib "awesome_lib_1") (part "R_0805_10k_150V_125mW_1%"))
    )
    (comp (ref "R6")
      (value "10k")
      (footprint "awesome_lib_1:RESC2012X60N")
      (description "R_0805_10k_150V_125mW_1%")
      (fields (field (name "POWER") "125mW") (field (name "TOLERANCE") "1%"))
      (libsource (lib "awesome_lib_1") (part "R_0805_10k_150V_125mW_1%"))
    )
    (comp (ref "R7")
      (value "4.7k")
      (footprint "awesome_lib_1:RESC2012X60N")
      (description "R_0805_4.7k_150V_125mW_1%")
      (fields (field (name "POWER") "125mW") (field (name "TOLERANCE") "1%"))
      (libsource (lib "awesome_lib_1") (part "R_0805_4.7k_150V_125mW_1%"))
    )
    (comp (ref "R8")
      (value "390R")
      (footprint "awesome_lib_1:RESC2012X60N")
      (description "R_0805_390R_150V_125mW_1%")
      (fields (field (name "POWER") "125mW") (field (name "TOLERANCE") "1%"))
      (libsource (lib "awesome_lib_1") (part "R_0805_390R_150V_125mW_1%"))
    )
    (comp (ref "R9")
      (value "390R")
      (footprint "awesome_lib_1:RESC2012X60N")
      (description "R_0805_390R_150V_125mW_1%")
      (fields (field (name "POWER") "125mW") (field (name "TOLERANCE") "1%"))
      (libsource (lib "awesome_lib_1") (part "R_0805_390R_150V_125mW_1%"))
    )
    (comp (ref "R10")
      (value "390R")
      (footprint "awesome_lib_1:RESC2012X60N")
      (description "R_0805_390R_150V_125mW_1%")
      (fields (field (name "POWER") "125mW") (field (name "TOLERANCE") "1%"))
      (libsource (lib "awesome_lib_1") (part "R_0805_390R_150V_125mW_1%"))
    )
    (comp (ref "R11")
      (value "390R")
      (footprint "awesome_lib_1:RESC2012X60N")
      (description "R_0805_390R_150V_125mW_1%")
      (fields (field (name "POWER") "125mW") (field (name "TOLERANCE") "1%"))
      (libsource (lib "awesome_lib_1") (part "R_0805_390R_150V_125mW_1%"))
    )
    (comp (ref "R12")
      (value "390R")
      (footprint "awesome_lib_1:RESC2012X60N")
      (description "R_0805_390R_150V_125mW_1%")
      (fields (field (name "POWER") "125mW") (field (name "TOLERANCE") "1%"))
      (libsource (lib "awesome_lib_1") (part "R_0805_390R_150V_125mW_1%"))
    )
    (comp (ref "R13")
      (value "390R")
      (footprint "awesome_lib_1:RESC2012X60N")
      (description "R_0805_390R_150V_125mW_1%")
      (fields (field (name "POWER") "125mW") (field (name "TOLERANCE") "1%"))
      (libsource (lib "awesome_lib_1") (part "R_0805_390R_150V_125mW_1%"))
    )
    (comp (ref "R14")
      (value "390R")
      (footprint "awesome_lib_1:RESC2012X60N")
      (description "R_0805_390R_150V_125mW_1%")
      (fields (field (name "POWER") "125mW") (field (name "TOLERANCE") "1%"))
      (libsource (lib "awesome_lib_1") (part "R_0805_390R_150V_125mW_1%"))
    )
    (comp (ref "R15")
      (value "390R")
      (footprint "awesome_lib_1:RESC2012X60N")
      (description "R_0805_390R_150V_125mW_1%")
      (fields (field (name "POWER") "125mW") (field (name "TOLERANCE") "1%"))
      (libsource (lib "awesome_lib_1") (part "R_0805_390R_150V_125mW_1%"))
    )
    (comp (ref "R16")
      (value "390R")
      (footprint "awesome_lib_1:RESC2012X60N")
      (description "R_0805_390R_150V_125mW_1%")
      (fields (field (name "POWER") "125mW") (field (name "TOLERANCE") "1%"))
      (libsource (lib "awesome_lib_1") (part "R_0805_390R_150V_125mW_1%"))
    )
    (comp (ref "R17")
      (value "10k")
      (footprint "awesome_lib_1:RESC2012X60N")
      (description "R_0805_10k_150V_125mW_1%")
      (fields (field (name "POWER") "125mW") (field (name "TOLERANCE") "1%"))
      (libsource (lib "awesome_lib_1") (part "R_0805_10k_150V_125mW_1%"))
    )
    (comp (ref "R18")
      (value "10k")
      (footprint "awesome_lib_1:RESC2012X60N")
      (description "R_0805_10k_150V_125mW_1%")
      (fields (field (name "POWER") "125mW") (field (name "TOLERANCE") "1%"))
      (libsource (lib "awesome_lib_1") (part "R_0805_10k_150V_125mW_1%"))
    )
    (comp (ref "R19")
      (value "10k")
      (footprint "awesome_lib_1:RESC2012X60N")
      (description "R_0805_10k_150V_125mW_1%")
      (fields (field (name "POWER") "125mW") (field (name "TOLERANCE") "1%"))
      (libsource (lib "awesome_lib_1") (part "R_0805_10k_150V_125mW_1%"))
    )
    (comp (ref "R20")
      (value "10k")
      (footprint "awesome_lib_1:RESC2012X60N")
      (description "R_0805_10k_150V_125mW_1%")
      (fields (field (name "POWER") "125mW") (field (name "TOLERANCE") "1%"))
      (libsource (lib "awesome_lib_1") (part "R_0805_10k_150V_125mW_1%"))
    )
    (comp (ref "R21")
      (value "10k")
      (footprint "awesome_lib_1:RESC2012X60N")
      (description "R_0805_10k_150V_125mW_1%")
      (fields (field (name "POWER") "125mW") (field (name "TOLERANCE") "1%"))
      (libsource (lib "awesome_lib_1") (part "R_0805_10k_150V_125mW_1%"))
    )
    (comp (ref "R22")
      (value "390R")
      (footprint "awesome_lib_1:RESC2012X60N")
      (description "R_0805_390R_150V_125mW_1%")
      (fields (field (name "POWER") "125mW") (field (name "TOLERANCE") "1%"))
      (libsource (lib "awesome_lib_1") (part "R_0805_390R_150V_125mW_1%"))
    )
    (comp (ref "R23")
      (value "390R")
      (footprint "awesome_lib_1:RESC2012X60N")
      (description "R_0805_390R_150V_125mW_1%")
      (fields (field (name "POWER") "125mW") (field (name "TOLERANCE") "1%"))
      (libsource (lib "awesome_lib_1") (part "R_0805_390R_150V_125mW_1%"))
    )
    (comp (ref "R24")
      (value "390R")
      (footprint "awesome_lib_1:RESC2012X60N")
      (description "R_0805_390R_150V_125mW_1%")
      (fields (field (name "POWER") "125mW") (field (name "TOLERANCE") "1%"))
      (libsource (lib "awesome_lib_1") (part "R_0805_390R_150V_125mW_1%"))
    )
    (comp (ref "R25")
      (value "10k")
      (footprint "awesome_lib_1:RESC2012X60N")
      (description "R_0805_10k_150V_125mW_1%")
      (fields (field (name "POWER") "125mW") (field (name "TOLERANCE") "1%"))
      (libsource (lib "awesome_lib_1") (part "R_0805_10k_150V_125mW_1%"))
    )
    (comp (ref "R26")
      (value "10k")
      (footprint "awesome_lib_1:RESC2012X60N")
      (description "R_0805_10k_150V_125mW_1%")
      (fields (field (name "POWER") "125mW") (field (name "TOLERANCE") "1%"))
      (libsource (lib "awesome_lib_1") (part "R_0805_10k_150V_125mW_1%"))
    )
    (comp (ref "R27")
      (value "10k")
      (footprint "awesome_lib_1:RESC2012X60N")
      (description "R_0805_10k_150V_125mW_1%")
      (fields (field (name "POWER") "125mW") (field (name "TOLERANCE") "1%"))
      (libsource (lib "awesome_lib_1") (part "R_0805_10k_150V_125mW_1%"))
    )
    (comp (ref "R28")
      (value "10k")
      (footprint "awesome_lib_1:RESC2012X60N")
      (description "R_0805_10k_150V_125mW_1%")
      (fields (field (name "POWER") "125mW") (field (name "TOLERANCE") "1%"))
      (libsource (lib "awesome_lib_1") (part "R_0805_10k_150V_125mW_1%"))
    )
    (comp (ref "RL1")
      (value "~")
      (footprint "awesome_lib_1:REL_HK19F_DC5V")
      (description "Miniature Relay for Signal Circuits")
      (fields (field (name "VOLTAGE") "5VDC") (field (name "MANUFACTURER") "HUI KE"))
      (libsource (lib "") (part "REL_HK19F_DC5V_2"))
    )
    (comp (ref "RL2")
      (value "~")
      (footprint "awesome_lib_1:REL_HK19F_DC5V")
      (description "Miniature Relay for Signal Circuits")
      (fields (field (name "VOLTAGE") "5VDC") (field (name "MANUFACTURER") "HUI KE"))
      (libsource (lib "awesome_lib_1") (part "REL_HK19F_DC5V"))
    )
    (comp (ref "RL3")
      (value "~")
      (footprint "awesome_lib_1:REL_HK19F_DC5V")
      (description "Miniature Relay for Signal Circuits")
      (fields
        (field (name "MANUFACTURER") "HUI KE")
        (field (name "MANUFACTURER PART NUMBER") "HK19F-DC5V-SHG")
      )
      (libsource (lib "awesome_lib_1") (part "REL_HK19F_DC5V"))
    )
    (comp (ref "RL4")
      (value "~")
      (footprint "awesome_lib_1:REL_HK19F_DC5V")
      (description "Miniature Relay for Signal Circuits")
      (fields
        (field (name "MANUFACTURER") "HUI KE")
        (field (name "MANUFACTURER PART NUMBER") "HK19F-DC5V-SHG")
      )
      (libsource (lib "awesome_lib_1") (part "REL_HK19F_DC5V"))
    )
    (comp (ref "RPI1")
      (value "RPI GPIO Connector")
      (footprint "awesome_lib_1:3M_N2540-6002RB")
      (description "GPIO Header for Raspberry Pi A+/B+/Pi 2/Pi 3 - 2x20")
      (fields
        (field (name "MANUFACTURER") "SparkFun Electronics")
        (field (name "MANUFACTURER PART NUMBER") "PRT-14017")
      )
      (libsource (lib "awesome_lib_1") (part "RPI GPIO Connector"))
    )
    (comp (ref "RPI2")
      (value "RPI 2B Board")
      (footprint "awesome_lib_1:RPi 2B Board")
      (fields (field (name "MANUFACTURER") "GENERIC"))
      (libsource (lib "awesome_lib_1") (part "RPI 2B Board"))
    )
    (comp (ref "T1")
      (value "FDS6679AZ")
      (footprint "awesome_lib_1:SOIC127P600X175-8N")
      (description "-30V -13A P-Channel PowerTrench MOSFET")
      (fields (field (name "MANUFACTURER") "On Semiconductor(ONS-FAIR)"))
      (libsource (lib "awesome_lib_1") (part "FDS6679AZ_Flip"))
    )
    (comp (ref "U1")
      (value "Arduino_Pro_Micro")
      (footprint "awesome_lib_1:Arduino_Pro_Micro")
      (libsource (lib "awesome_lib_1") (part "Arduino_Pro_Micro"))
    )
    (comp (ref "VC1")
      (value "USB Video Capture")
      (footprint "awesome_lib_1:USB_Video_Capture")
      (fields (field (name "MANUFACTURER") "GENERIC"))
      (libsource (lib "awesome_lib_1") (part "USB Video Capture"))
    )
    (comp (ref "VC2")
      (value "VGA_to_Composite")
      (footprint "awesome_lib_1:VGA_to_Composite")
      (fields (field (name "MANUFACTURER") "GENERIC"))
      (libsource (lib "awesome_lib_1") (part "VGA_to_Composite"))
    )
  )
  (nets
    (net (code "1") (name "/ISP_MISO") (class "Default")
      (node (ref "J12") (pin "1") (pinfunction "1_1") (pintype "passive"))
      (node (ref "U1") (pin "15") (pinfunction "14_15") (pintype "bidirectional"))
    )
    (net (code "2") (name "/ISP_MOSI") (class "Default")
      (node (ref "J12") (pin "4") (pinfunction "4_4") (pintype "passive"))
      (node (ref "U1") (pin "14") (pinfunction "16_14") (pintype "bidirectional"))
    )
    (net (code "3") (name "/ISP_RST") (class "Default")
      (node (ref "C20") (pin "1") (pinfunction "1_1") (pintype "passive"))
      (node (ref "J11") (pin "2") (pinfunction "2_2") (pintype "passive"))
      (node (ref "J12") (pin "5") (pinfunction "5_5") (pintype "passive"))
      (node (ref "R17") (pin "2") (pinfunction "2_2") (pintype "passive"))
      (node (ref "U1") (pin "22") (pinfunction "RST_22") (pintype "input"))
    )
    (net (code "4") (name "/ISP_SCK") (class "Default")
      (node (ref "J12") (pin "3") (pinfunction "3_3") (pintype "passive"))
      (node (ref "U1") (pin "16") (pinfunction "15_16") (pintype "bidirectional"))
    )
    (net (code "5") (name "/Ic_2") (class "Default")
      (node (ref "J13") (pin "2") (pinfunction "2_2") (pintype "passive"))
      (node (ref "J14") (pin "2") (pinfunction "2_2") (pintype "passive"))
    )
    (net (code "6") (name "/Ic_4") (class "Default")
      (node (ref "J13") (pin "4") (pinfunction "4_4") (pintype "passive"))
      (node (ref "J14") (pin "4") (pinfunction "4_4") (pintype "passive"))
    )
    (net (code "7") (name "/Ic_6") (class "Default")
      (node (ref "J13") (pin "6") (pinfunction "6_6") (pintype "passive"))
      (node (ref "J14") (pin "6") (pinfunction "6_6") (pintype "passive"))
    )
    (net (code "8") (name "/Ic_7") (class "Default")
      (node (ref "J13") (pin "7") (pinfunction "7_7") (pintype "passive"))
      (node (ref "J14") (pin "7") (pinfunction "7_7") (pintype "passive"))
    )
    (net (code "9") (name "/Ic_8") (class "Default")
      (node (ref "J13") (pin "8") (pinfunction "8_8") (pintype "passive"))
      (node (ref "J14") (pin "8") (pinfunction "8_8") (pintype "passive"))
    )
    (net (code "10") (name "/Ic_9") (class "Default")
      (node (ref "J13") (pin "9") (pinfunction "9_9") (pintype "passive"))
      (node (ref "J14") (pin "9") (pinfunction "9_9") (pintype "passive"))
    )
    (net (code "11") (name "/Ic_10") (class "Default")
      (node (ref "J13") (pin "10") (pinfunction "10_10") (pintype "passive"))
      (node (ref "J14") (pin "10") (pinfunction "10_10") (pintype "passive"))
    )
    (net (code "12") (name "/Ic_11") (class "Default")
      (node (ref "J13") (pin "11") (pinfunction "11_11") (pintype "passive"))
      (node (ref "J14") (pin "11") (pinfunction "11_11") (pintype "passive"))
    )
    (net (code "13") (name "/Ic_12") (class "Default")
      (node (ref "J13") (pin "12") (pinfunction "12_12") (pintype "passive"))
      (node (ref "J14") (pin "12") (pinfunction "12_12") (pintype "passive"))
    )
    (net (code "14") (name "/Ic_13") (class "Default")
      (node (ref "J13") (pin "13") (pinfunction "13_13") (pintype "passive"))
      (node (ref "J14") (pin "13") (pinfunction "13_13") (pintype "passive"))
    )
    (net (code "15") (name "/Ic_14") (class "Default")
      (node (ref "J13") (pin "14") (pinfunction "14_14") (pintype "passive"))
      (node (ref "J14") (pin "14") (pinfunction "14_14") (pintype "passive"))
    )
    (net (code "16") (name "/Ic_15") (class "Default")
      (node (ref "J13") (pin "15") (pinfunction "15_15") (pintype "passive"))
      (node (ref "J14") (pin "15") (pinfunction "15_15") (pintype "passive"))
    )
    (net (code "17") (name "/Ic_16") (class "Default")
      (node (ref "J13") (pin "16") (pinfunction "16_16") (pintype "passive"))
      (node (ref "J14") (pin "16") (pinfunction "16_16") (pintype "passive"))
    )
    (net (code "18") (name "/Ic_17") (class "Default")
      (node (ref "J13") (pin "17") (pinfunction "17_17") (pintype "passive"))
      (node (ref "J14") (pin "17") (pinfunction "17_17") (pintype "passive"))
    )
    (net (code "19") (name "/Ic_18") (class "Default")
      (node (ref "J13") (pin "18") (pinfunction "18_18") (pintype "passive"))
      (node (ref "J14") (pin "18") (pinfunction "18_18") (pintype "passive"))
    )
    (net (code "20") (name "/Ic_25") (class "Default")
      (node (ref "J13") (pin "25") (pinfunction "25_25") (pintype "passive"))
      (node (ref "J14") (pin "25") (pinfunction "25_25") (pintype "passive"))
    )
    (net (code "21") (name "/Ic_32") (class "Default")
      (node (ref "J13") (pin "32") (pinfunction "32_32") (pintype "passive"))
      (node (ref "J14") (pin "32") (pinfunction "32_32") (pintype "passive"))
    )
    (net (code "22") (name "/Ic_33") (class "Default")
      (node (ref "J13") (pin "33") (pinfunction "33_33") (pintype "passive"))
      (node (ref "J14") (pin "33") (pinfunction "33_33") (pintype "passive"))
    )
    (net (code "23") (name "/Ic_37") (class "Default")
      (node (ref "J13") (pin "37") (pinfunction "37_37") (pintype "passive"))
      (node (ref "J14") (pin "37") (pinfunction "37_37") (pintype "passive"))
    )
    (net (code "24") (name "/KMA_RX") (class "Default")
      (node (ref "J10") (pin "1") (pinfunction "1_1") (pintype "passive"))
      (node (ref "Q7") (pin "3") (pinfunction "D_3") (pintype "passive"))
      (node (ref "R28") (pin "2") (pinfunction "2_2") (pintype "passive"))
    )
    (net (code "25") (name "/KMA_Rst") (class "Default")
      (node (ref "R24") (pin "1") (pinfunction "1_1") (pintype "passive"))
      (node (ref "RPI1") (pin "7") (pinfunction "GPIO4_7") (pintype "bidirectional"))
    )
    (net (code "26") (name "/KMA_TX") (class "Default")
      (node (ref "J10") (pin "3") (pinfunction "3_3") (pintype "passive"))
      (node (ref "Q4") (pin "3") (pinfunction "D_3") (pintype "passive"))
      (node (ref "R21") (pin "2") (pinfunction "2_2") (pintype "passive"))
    )
    (net (code "27") (name "/LP1_1") (class "Default")
      (node (ref "J1") (pin "1") (pinfunction "1_1") (pintype "bidirectional"))
      (node (ref "R2") (pin "1") (pinfunction "1_1") (pintype "passive"))
    )
    (net (code "28") (name "/LP1_2") (class "Default")
      (node (ref "IC1") (pin "2") (pinfunction "K_2") (pintype "input"))
      (node (ref "J1") (pin "2") (pinfunction "2_2") (pintype "bidirectional"))
    )
    (net (code "29") (name "/LP2_1") (class "Default")
      (node (ref "J1") (pin "3") (pinfunction "3_3") (pintype "bidirectional"))
      (node (ref "R8") (pin "1") (pinfunction "1_1") (pintype "passive"))
    )
    (net (code "30") (name "/LP2_2") (class "Default")
      (node (ref "IC2") (pin "2") (pinfunction "K_2") (pintype "input"))
      (node (ref "J1") (pin "6") (pinfunction "6_6") (pintype "bidirectional"))
    )
    (net (code "31") (name "/LP3_1") (class "Default")
      (node (ref "IC3") (pin "3") (pinfunction "C_3") (pintype "open_collector"))
      (node (ref "J1") (pin "5") (pinfunction "5_5") (pintype "bidirectional"))
    )
    (net (code "32") (name "/LP3_2") (class "Default")
      (node (ref "IC3") (pin "4") (pinfunction "E_4") (pintype "open_emitter"))
      (node (ref "J1") (pin "4") (pinfunction "4_4") (pintype "bidirectional"))
    )
    (net (code "33") (name "/LP4_1") (class "Default")
      (node (ref "IC4") (pin "3") (pinfunction "C_3") (pintype "open_collector"))
      (node (ref "J1") (pin "7") (pinfunction "7_7") (pintype "bidirectional"))
    )
    (net (code "34") (name "/LP4_2") (class "Default")
      (node (ref "IC4") (pin "4") (pinfunction "E_4") (pintype "open_emitter"))
      (node (ref "J1") (pin "8") (pinfunction "8_8") (pintype "bidirectional"))
    )
    (net (code "35") (name "/MSD_A_N") (class "Default")
      (node (ref "J6") (pin "2") (pinfunction "-D_2") (pintype "bidirectional"))
      (node (ref "RL2") (pin "4") (pinfunction "C_4") (pintype "bidirectional"))
    )
    (net (code "36") (name "/MSD_A_P") (class "Default")
      (node (ref "J6") (pin "3") (pinfunction "+D_3") (pintype "bidirectional"))
      (node (ref "RL2") (pin "13") (pinfunction "C_13") (pintype "bidirectional"))
    )
    (net (code "37") (name "/MSD_B_N") (class "Default")
      (node (ref "RL2") (pin "6") (pinfunction "NC_6") (pintype "bidirectional"))
      (node (ref "RPI2") (pin "ADM") (pinfunction "ADM_ADM") (pintype "bidirectional"))
    )
    (net (code "38") (name "/MSD_B_P") (class "Default")
      (node (ref "RL2") (pin "11") (pinfunction "NC_11") (pintype "bidirectional"))
      (node (ref "RPI2") (pin "ADP") (pinfunction "ADP_ADP") (pintype "bidirectional"))
    )
    (net (code "39") (name "/MSD_C_N") (class "Default")
      (node (ref "J7") (pin "2") (pinfunction "-D_2") (pintype "bidirectional"))
      (node (ref "RL2") (pin "8") (pinfunction "NO_8") (pintype "bidirectional"))
    )
    (net (code "40") (name "/MSD_C_P") (class "Default")
      (node (ref "J7") (pin "3") (pinfunction "+D_3") (pintype "bidirectional"))
      (node (ref "RL2") (pin "9") (pinfunction "NO_9") (pintype "bidirectional"))
    )
    (net (code "41") (name "/MSD_Rst") (class "Default")
      (node (ref "R3") (pin "1") (pinfunction "1_1") (pintype "passive"))
      (node (ref "RPI1") (pin "33") (pinfunction "GPIO13_33") (pintype "bidirectional"))
    )
    (net (code "42") (name "/MSD_Target") (class "Default")
      (node (ref "R4") (pin "1") (pinfunction "1_1") (pintype "passive"))
      (node (ref "R9") (pin "1") (pinfunction "1_1") (pintype "passive"))
      (node (ref "RPI1") (pin "32") (pinfunction "GPIO12_32") (pintype "bidirectional"))
    )
    (net (code "43") (name "/RP1_1") (class "Default")
      (node (ref "J2") (pin "1") (pinfunction "1_1") (pintype "bidirectional"))
      (node (ref "J3") (pin "1") (pinfunction "1_1") (pintype "passive"))
      (node (ref "J3") (pin "2") (pinfunction "2_2") (pintype "passive"))
    )
    (net (code "44") (name "/RP1_2") (class "Default")
      (node (ref "J2") (pin "2") (pinfunction "2_2") (pintype "bidirectional"))
      (node (ref "J3") (pin "3") (pinfunction "3_3") (pintype "passive"))
      (node (ref "J3") (pin "4") (pinfunction "4_4") (pintype "passive"))
      (node (ref "J3") (pin "5") (pinfunction "5_5") (pintype "passive"))
      (node (ref "J3") (pin "6") (pinfunction "6_6") (pintype "passive"))
    )
    (net (code "45") (name "/RP2_1") (class "Default")
      (node (ref "J2") (pin "3") (pinfunction "3_3") (pintype "bidirectional"))
      (node (ref "J4") (pin "1") (pinfunction "1_1") (pintype "passive"))
      (node (ref "J4") (pin "2") (pinfunction "2_2") (pintype "passive"))
    )
    (net (code "46") (name "/RP2_2") (class "Default")
      (node (ref "J2") (pin "6") (pinfunction "6_6") (pintype "bidirectional"))
      (node (ref "J4") (pin "3") (pinfunction "3_3") (pintype "passive"))
      (node (ref "J4") (pin "4") (pinfunction "4_4") (pintype "passive"))
    )
    (net (code "47") (name "/RP3_1") (class "Default")
      (node (ref "J2") (pin "5") (pinfunction "5_5") (pintype "bidirectional"))
      (node (ref "J5") (pin "1") (pinfunction "1_1") (pintype "passive"))
      (node (ref "J5") (pin "2") (pinfunction "2_2") (pintype "passive"))
    )
    (net (code "48") (name "/RP3_2") (class "Default")
      (node (ref "J2") (pin "4") (pinfunction "4_4") (pintype "bidirectional"))
      (node (ref "J5") (pin "3") (pinfunction "3_3") (pintype "passive"))
      (node (ref "J5") (pin "4") (pinfunction "4_4") (pintype "passive"))
    )
    (net (code "49") (name "/RP4_1") (class "Default")
      (node (ref "J2") (pin "7") (pinfunction "7_7") (pintype "bidirectional"))
      (node (ref "J8") (pin "1") (pinfunction "1_1") (pintype "passive"))
      (node (ref "J8") (pin "2") (pinfunction "2_2") (pintype "passive"))
    )
    (net (code "50") (name "/RP4_2") (class "Default")
      (node (ref "J2") (pin "8") (pinfunction "8_8") (pintype "bidirectional"))
      (node (ref "J8") (pin "3") (pinfunction "3_3") (pintype "passive"))
      (node (ref "J8") (pin "4") (pinfunction "4_4") (pintype "passive"))
    )
    (net (code "51") (name "/RPi_HDD") (class "Default")
      (node (ref "R13") (pin "1") (pinfunction "1_1") (pintype "passive"))
      (node (ref "RPI1") (pin "37") (pinfunction "GPIO26_37") (pintype "bidirectional"))
    )
    (net (code "52") (name "/RPi_Led_GND") (class "Default")
      (node (ref "LD2") (pin "1") (pinfunction "C_1") (pintype "passive"))
      (node (ref "LD2") (pin "3") (pinfunction "C_3") (pintype "passive"))
      (node (ref "RPI1") (pin "25") (pinfunction "GND_25") (pintype "power_in"))
    )
    (net (code "53") (name "/RPi_RX") (class "Default")
      (node (ref "Q4") (pin "2") (pinfunction "S_2") (pintype "passive"))
      (node (ref "R20") (pin "2") (pinfunction "2_2") (pintype "passive"))
      (node (ref "RPI1") (pin "10") (pinfunction "UART0_RX_10") (pintype "bidirectional"))
    )
    (net (code "54") (name "/RPi_TX") (class "Default")
      (node (ref "Q7") (pin "2") (pinfunction "S_2") (pintype "passive"))
      (node (ref "R27") (pin "2") (pinfunction "2_2") (pintype "passive"))
      (node (ref "RPI1") (pin "8") (pinfunction "UART0_TX_8") (pintype "bidirectional"))
    )
    (net (code "55") (name "/Srv_B_Pwr") (class "Default")
      (node (ref "R14") (pin "1") (pinfunction "1_1") (pintype "passive"))
      (node (ref "RPI1") (pin "13") (pinfunction "GPIO27_13") (pintype "bidirectional"))
    )
    (net (code "56") (name "/Srv_B_Rst") (class "Default")
      (node (ref "R11") (pin "1") (pinfunction "1_1") (pintype "passive"))
      (node (ref "RPI1") (pin "16") (pinfunction "GPIO23_16") (pintype "bidirectional"))
    )
    (net (code "57") (name "/Srv_L_HDD") (class "Default")
      (node (ref "IC2") (pin "4") (pinfunction "E_4") (pintype "open_emitter"))
      (node (ref "R7") (pin "2") (pinfunction "2_2") (pintype "passive"))
      (node (ref "RPI1") (pin "15") (pinfunction "GPIO22_15") (pintype "bidirectional"))
    )
    (net (code "58") (name "/Srv_L_Power") (class "Default")
      (node (ref "IC1") (pin "4") (pinfunction "E_4") (pintype "open_emitter"))
      (node (ref "R1") (pin "2") (pinfunction "2_2") (pintype "passive"))
      (node (ref "RPI1") (pin "18") (pinfunction "GPIO24_18") (pintype "bidirectional"))
    )
    (net (code "59") (name "/VCS_B_M") (class "Default")
      (node (ref "J16") (pin "2") (pinfunction "-D_2") (pintype "bidirectional"))
      (node (ref "RPI2") (pin "BDM") (pinfunction "BDM_BDM") (pintype "bidirectional"))
    )
    (net (code "60") (name "/VCS_B_P") (class "Default")
      (node (ref "J16") (pin "3") (pinfunction "+D_3") (pintype "bidirectional"))
      (node (ref "RPI2") (pin "BDP") (pinfunction "BDP_BDP") (pintype "bidirectional"))
    )
    (net (code "61") (name "/Video_Vcc_1") (class "Default")
      (node (ref "R15") (pin "1") (pinfunction "1_1") (pintype "passive"))
      (node (ref "RPI1") (pin "11") (pinfunction "GPIO17_11") (pintype "bidirectional"))
    )
    (net (code "62") (name "/Video_Vcc_2") (class "Default")
      (node (ref "R22") (pin "1") (pinfunction "1_1") (pintype "passive"))
      (node (ref "RPI1") (pin "12") (pinfunction "GPIO18_12") (pintype "bidirectional"))
    )
    (net (code "63") (name "GND") (class "Default")
      (node (ref "C1") (pin "2") (pinfunction "2_2") (pintype "passive"))
      (node (ref "C10") (pin "2") (pinfunction "2_2") (pintype "passive"))
      (node (ref "C11") (pin "2") (pinfunction "2_2") (pintype "passive"))
      (node (ref "C12") (pin "2") (pinfunction "2_2") (pintype "passive"))
      (node (ref "C13") (pin "2") (pinfunction "2_2") (pintype "passive"))
      (node (ref "C14") (pin "2") (pinfunction "2_2") (pintype "passive"))
      (node (ref "C15") (pin "2") (pinfunction "2_2") (pintype "passive"))
      (node (ref "C16") (pin "2") (pinfunction "2_2") (pintype "passive"))
      (node (ref "C17") (pin "2") (pinfunction "2_2") (pintype "passive"))
      (node (ref "C18") (pin "2") (pinfunction "2_2") (pintype "passive"))
      (node (ref "C19") (pin "2") (pinfunction "2_2") (pintype "passive"))
      (node (ref "C2") (pin "2") (pinfunction "2_2") (pintype "passive"))
      (node (ref "C20") (pin "2") (pinfunction "2_2") (pintype "passive"))
      (node (ref "C21") (pin "2") (pinfunction "2_2") (pintype "passive"))
      (node (ref "C22") (pin "2") (pinfunction "2_2") (pintype "passive"))
      (node (ref "C23") (pin "2") (pinfunction "2_2") (pintype "passive"))
      (node (ref "C24") (pin "2") (pinfunction "2_2") (pintype "passive"))
      (node (ref "C25") (pin "2") (pinfunction "2_2") (pintype "passive"))
      (node (ref "C26") (pin "2") (pinfunction "2_2") (pintype "passive"))
      (node (ref "C27") (pin "2") (pinfunction "2_2") (pintype "passive"))
      (node (ref "C28") (pin "2") (pinfunction "2_2") (pintype "passive"))
      (node (ref "C29") (pin "2") (pinfunction "2_2") (pintype "passive"))
      (node (ref "C3") (pin "2") (pinfunction "2_2") (pintype "passive"))
      (node (ref "C30") (pin "2") (pinfunction "2_2") (pintype "passive"))
      (node (ref "C31") (pin "2") (pinfunction "2_2") (pintype "passive"))
      (node (ref "C32") (pin "2") (pinfunction "2_2") (pintype "passive"))
      (node (ref "C33") (pin "2") (pinfunction "2_2") (pintype "passive"))
      (node (ref "C34") (pin "2") (pinfunction "2_2") (pintype "passive"))
      (node (ref "C4") (pin "2") (pinfunction "2_2") (pintype "passive"))
      (node (ref "C5") (pin "2") (pinfunction "2_2") (pintype "passive"))
      (node (ref "C6") (pin "2") (pinfunction "2_2") (pintype "passive"))
      (node (ref "C7") (pin "2") (pinfunction "2_2") (pintype "passive"))
      (node (ref "C8") (pin "2") (pinfunction "2_2") (pintype "passive"))
      (node (ref "C9") (pin "2") (pinfunction "2_2") (pintype "passive"))
      (node (ref "D5") (pin "2") (pinfunction "A_2") (pintype "passive"))
      (node (ref "IC1") (pin "3") (pinfunction "C_3") (pintype "open_collector"))
      (node (ref "IC2") (pin "3") (pinfunction "C_3") (pintype "open_collector"))
      (node (ref "IC3") (pin "2") (pinfunction "K_2") (pintype "input"))
      (node (ref "IC4") (pin "2") (pinfunction "K_2") (pintype "input"))
      (node (ref "J12") (pin "6") (pinfunction "6_6") (pintype "passive"))
      (node (ref "J15") (pin "1") (pinfunction "1_1") (pintype "passive"))
      (node (ref "J16") (pin "4") (pinfunction "GND_4") (pintype "bidirectional"))
      (node (ref "J16") (pin "5") (pinfunction "SHIELD_5") (pintype "power_in"))
      (node (ref "J6") (pin "4") (pinfunction "GND_4") (pintype "bidirectional"))
      (node (ref "J6") (pin "5") (pinfunction "SHIELD_5") (pintype "power_in"))
      (node (ref "J7") (pin "4") (pinfunction "GND_4") (pintype "bidirectional"))
      (node (ref "J7") (pin "5") (pinfunction "SHIELD_5") (pintype "power_in"))
      (node (ref "J9") (pin "3") (pinfunction "3_3") (pintype "power_in"))
      (node (ref "LD1") (pin "1") (pinfunction "C_1") (pintype "passive"))
      (node (ref "LD1") (pin "3") (pinfunction "C_3") (pintype "passive"))
      (node (ref "LD3") (pin "1") (pinfunction "C_1") (pintype "passive"))
      (node (ref "LD3") (pin "3") (pinfunction "C_3") (pintype "passive"))
      (node (ref "Q1") (pin "2") (pinfunction "S_2") (pintype "passive"))
      (node (ref "Q2") (pin "2") (pinfunction "S_2") (pintype "passive"))
      (node (ref "Q3") (pin "2") (pinfunction "S_2") (pintype "passive"))
      (node (ref "Q5") (pin "2") (pinfunction "S_2") (pintype "passive"))
      (node (ref "Q6") (pin "2") (pinfunction "S_2") (pintype "passive"))
      (node (ref "R18") (pin "2") (pinfunction "2_2") (pintype "passive"))
      (node (ref "R19") (pin "2") (pinfunction "2_2") (pintype "passive"))
      (node (ref "R25") (pin "2") (pinfunction "2_2") (pintype "passive"))
      (node (ref "R26") (pin "2") (pinfunction "2_2") (pintype "passive"))
      (node (ref "R5") (pin "2") (pinfunction "2_2") (pintype "passive"))
      (node (ref "R6") (pin "2") (pinfunction "2_2") (pintype "passive"))
      (node (ref "RPI1") (pin "14") (pinfunction "GND_14") (pintype "power_in"))
      (node (ref "RPI1") (pin "6") (pinfunction "GND_6") (pintype "power_in"))
      (node (ref "RPI1") (pin "9") (pinfunction "GND_9") (pintype "power_in"))
      (node (ref "U1") (pin "23") (pinfunction "GND_23") (pintype "power_in"))
      (node (ref "U1") (pin "3") (pinfunction "GND_3") (pintype "power_in"))
      (node (ref "U1") (pin "4") (pinfunction "GND_4") (pintype "power_in"))
      (node (ref "VC2") (pin "2") (pinfunction "Gnd_2") (pintype "power_in"))
    )
    (net (code "64") (name "MSD_Vcc") (class "Default")
      (node (ref "C5") (pin "1") (pinfunction "1_1") (pintype "passive"))
      (node (ref "C6") (pin "1") (pinfunction "1_1") (pintype "passive"))
      (node (ref "J6") (pin "1") (pinfunction "VBUS_1") (pintype "bidirectional"))
      (node (ref "L1") (pin "2") (pinfunction "2_2") (pintype "passive"))
    )
    (net (code "65") (name "Main_Vcc") (class "Default")
      (node (ref "C1") (pin "1") (pinfunction "1_1") (pintype "passive"))
      (node (ref "C10") (pin "1") (pinfunction "1_1") (pintype "passive"))
      (node (ref "C11") (pin "1") (pinfunction "1_1") (pintype "passive"))
      (node (ref "C2") (pin "1") (pinfunction "1_1") (pintype "passive"))
      (node (ref "C21") (pin "1") (pinfunction "1_1") (pintype "passive"))
      (node (ref "C22") (pin "1") (pinfunction "1_1") (pintype "passive"))
      (node (ref "C23") (pin "1") (pinfunction "1_1") (pintype "passive"))
      (node (ref "C28") (pin "1") (pinfunction "1_1") (pintype "passive"))
      (node (ref "C29") (pin "1") (pinfunction "1_1") (pintype "passive"))
      (node (ref "C7") (pin "1") (pinfunction "1_1") (pintype "passive"))
      (node (ref "C9") (pin "1") (pinfunction "1_1") (pintype "passive"))
      (node (ref "D1") (pin "1") (pinfunction "K_1") (pintype "passive"))
      (node (ref "D2") (pin "1") (pinfunction "K_1") (pintype "passive"))
      (node (ref "D3") (pin "1") (pinfunction "K_1") (pintype "passive"))
      (node (ref "D4") (pin "2") (pinfunction "A_2") (pintype "passive"))
      (node (ref "D5") (pin "1") (pinfunction "K_1") (pintype "passive"))
      (node (ref "D6") (pin "1") (pinfunction "K_1") (pintype "passive"))
      (node (ref "L2") (pin "2") (pinfunction "2_2") (pintype "passive"))
      (node (ref "L5") (pin "1") (pinfunction "1_1") (pintype "passive"))
      (node (ref "RL1") (pin "11") (pinfunction "NC_11") (pintype "bidirectional"))
      (node (ref "RL1") (pin "16") (pinfunction "16_16") (pintype "passive"))
      (node (ref "RL1") (pin "6") (pinfunction "NC_6") (pintype "bidirectional"))
      (node (ref "RL2") (pin "16") (pinfunction "16_16") (pintype "passive"))
      (node (ref "RL3") (pin "13") (pinfunction "C_13") (pintype "bidirectional"))
      (node (ref "RL3") (pin "16") (pinfunction "16_16") (pintype "passive"))
      (node (ref "RL3") (pin "4") (pinfunction "C_4") (pintype "bidirectional"))
      (node (ref "RL4") (pin "13") (pinfunction "C_13") (pintype "bidirectional"))
      (node (ref "RL4") (pin "16") (pinfunction "16_16") (pintype "passive"))
      (node (ref "RL4") (pin "4") (pinfunction "C_4") (pintype "bidirectional"))
    )
    (net (code "66") (name "Net-(C8-Pad1)") (class "Default")
      (node (ref "C8") (pin "1") (pinfunction "1_1") (pintype "passive"))
      (node (ref "L2") (pin "1") (pinfunction "1_1") (pintype "passive"))
      (node (ref "T1") (pin "1") (pinfunction "S_1") (pintype "passive"))
      (node (ref "T1") (pin "2") (pinfunction "S_2") (pintype "passive"))
      (node (ref "T1") (pin "3") (pinfunction "S_3") (pintype "passive"))
    )
    (net (code "67") (name "Net-(D1-A)") (class "Default")
      (node (ref "D1") (pin "2") (pinfunction "A_2") (pintype "passive"))
      (node (ref "Q1") (pin "3") (pinfunction "D_3") (pintype "passive"))
      (node (ref "RL1") (pin "1") (pinfunction "1_1") (pintype "passive"))
    )
    (net (code "68") (name "Net-(D2-A)") (class "Default")
      (node (ref "D2") (pin "2") (pinfunction "A_2") (pintype "passive"))
      (node (ref "Q2") (pin "3") (pinfunction "D_3") (pintype "passive"))
      (node (ref "RL2") (pin "1") (pinfunction "1_1") (pintype "passive"))
    )
    (net (code "69") (name "Net-(D3-A)") (class "Default")
      (node (ref "D3") (pin "2") (pinfunction "A_2") (pintype "passive"))
      (node (ref "Q3") (pin "3") (pinfunction "D_3") (pintype "passive"))
      (node (ref "RL3") (pin "1") (pinfunction "1_1") (pintype "passive"))
    )
    (net (code "70") (name "Net-(D4-K)") (class "Default")
      (node (ref "C16") (pin "1") (pinfunction "1_1") (pintype "passive"))
      (node (ref "C17") (pin "1") (pinfunction "1_1") (pintype "passive"))
      (node (ref "D4") (pin "1") (pinfunction "K_1") (pintype "passive"))
      (node (ref "L4") (pin "1") (pinfunction "1_1") (pintype "passive"))
    )
    (net (code "71") (name "Net-(D6-A)") (class "Default")
      (node (ref "D6") (pin "2") (pinfunction "A_2") (pintype "passive"))
      (node (ref "Q5") (pin "3") (pinfunction "D_3") (pintype "passive"))
      (node (ref "RL4") (pin "1") (pinfunction "1_1") (pintype "passive"))
    )
    (net (code "72") (name "Net-(IC1-A)") (class "Default")
      (node (ref "IC1") (pin "1") (pinfunction "A_1") (pintype "input"))
      (node (ref "R2") (pin "2") (pinfunction "2_2") (pintype "passive"))
    )
    (net (code "73") (name "Net-(IC2-A)") (class "Default")
      (node (ref "IC2") (pin "1") (pinfunction "A_1") (pintype "input"))
      (node (ref "R8") (pin "2") (pinfunction "2_2") (pintype "passive"))
    )
    (net (code "74") (name "Net-(IC3-A)") (class "Default")
      (node (ref "IC3") (pin "1") (pinfunction "A_1") (pintype "input"))
      (node (ref "R11") (pin "2") (pinfunction "2_2") (pintype "passive"))
    )
    (net (code "75") (name "Net-(IC4-A)") (class "Default")
      (node (ref "IC4") (pin "1") (pinfunction "A_1") (pintype "input"))
      (node (ref "R14") (pin "2") (pinfunction "2_2") (pintype "passive"))
    )
    (net (code "76") (name "Net-(J9-Pad1)") (class "Default")
      (node (ref "J9") (pin "1") (pinfunction "1_1") (pintype "power_in"))
      (node (ref "T1") (pin "5") (pinfunction "D_5") (pintype "passive"))
      (node (ref "T1") (pin "6") (pinfunction "D_6") (pintype "passive"))
      (node (ref "T1") (pin "7") (pinfunction "D_7") (pintype "passive"))
      (node (ref "T1") (pin "8") (pinfunction "D_8") (pintype "passive"))
    )
    (net (code "77") (name "Net-(LD1A-A)") (class "Default")
      (node (ref "LD1") (pin "2") (pinfunction "A_2") (pintype "passive"))
      (node (ref "R10") (pin "2") (pinfunction "2_2") (pintype "passive"))
    )
    (net (code "78") (name "Net-(LD1B-A)") (class "Default")
      (node (ref "LD1") (pin "4") (pinfunction "A_4") (pintype "passive"))
      (node (ref "R9") (pin "2") (pinfunction "2_2") (pintype "passive"))
    )
    (net (code "79") (name "Net-(LD2A-A)") (class "Default")
      (node (ref "LD2") (pin "2") (pinfunction "A_2") (pintype "passive"))
      (node (ref "R12") (pin "2") (pinfunction "2_2") (pintype "passive"))
    )
    (net (code "80") (name "Net-(LD2B-A)") (class "Default")
      (node (ref "LD2") (pin "4") (pinfunction "A_4") (pintype "passive"))
      (node (ref "R13") (pin "2") (pinfunction "2_2") (pintype "passive"))
    )
    (net (code "81") (name "Net-(LD3A-A)") (class "Default")
      (node (ref "LD3") (pin "2") (pinfunction "A_2") (pintype "passive"))
      (node (ref "R23") (pin "2") (pinfunction "2_2") (pintype "passive"))
    )
    (net (code "82") (name "Net-(LD3B-A)") (class "Default")
      (node (ref "LD3") (pin "4") (pinfunction "A_4") (pintype "passive"))
      (node (ref "R16") (pin "2") (pinfunction "2_2") (pintype "passive"))
    )
    (net (code "83") (name "Net-(Q1-G)") (class "Default")
      (node (ref "Q1") (pin "1") (pinfunction "G_1") (pintype "passive"))
      (node (ref "R3") (pin "2") (pinfunction "2_2") (pintype "passive"))
      (node (ref "R5") (pin "1") (pinfunction "1_1") (pintype "passive"))
    )
    (net (code "84") (name "Net-(Q2-G)") (class "Default")
      (node (ref "Q2") (pin "1") (pinfunction "G_1") (pintype "passive"))
      (node (ref "R4") (pin "2") (pinfunction "2_2") (pintype "passive"))
      (node (ref "R6") (pin "1") (pinfunction "1_1") (pintype "passive"))
    )
    (net (code "85") (name "Net-(Q3-G)") (class "Default")
      (node (ref "Q3") (pin "1") (pinfunction "G_1") (pintype "passive"))
      (node (ref "R15") (pin "2") (pinfunction "2_2") (pintype "passive"))
      (node (ref "R18") (pin "1") (pinfunction "1_1") (pintype "passive"))
    )
    (net (code "86") (name "Net-(Q5-G)") (class "Default")
      (node (ref "Q5") (pin "1") (pinfunction "G_1") (pintype "passive"))
      (node (ref "R22") (pin "2") (pinfunction "2_2") (pintype "passive"))
      (node (ref "R25") (pin "1") (pinfunction "1_1") (pintype "passive"))
    )
    (net (code "87") (name "Net-(Q6-D)") (class "Default")
      (node (ref "J11") (pin "1") (pinfunction "1_1") (pintype "passive"))
      (node (ref "Q6") (pin "3") (pinfunction "D_3") (pintype "passive"))
    )
    (net (code "88") (name "Net-(Q6-G)") (class "Default")
      (node (ref "Q6") (pin "1") (pinfunction "G_1") (pintype "passive"))
      (node (ref "R24") (pin "2") (pinfunction "2_2") (pintype "passive"))
      (node (ref "R26") (pin "1") (pinfunction "1_1") (pintype "passive"))
    )
    (net (code "89") (name "Net-(RL1B-C)") (class "Default")
      (node (ref "C3") (pin "1") (pinfunction "1_1") (pintype "passive"))
      (node (ref "C4") (pin "1") (pinfunction "1_1") (pintype "passive"))
      (node (ref "L1") (pin "1") (pinfunction "1_1") (pintype "passive"))
      (node (ref "R10") (pin "1") (pinfunction "1_1") (pintype "passive"))
      (node (ref "RL1") (pin "13") (pinfunction "C_13") (pintype "bidirectional"))
      (node (ref "RL1") (pin "4") (pinfunction "C_4") (pintype "bidirectional"))
    )
    (net (code "90") (name "Net-(RL3B-NO)") (class "Default")
      (node (ref "C12") (pin "1") (pinfunction "1_1") (pintype "passive"))
      (node (ref "C13") (pin "1") (pinfunction "1_1") (pintype "passive"))
      (node (ref "L3") (pin "1") (pinfunction "1_1") (pintype "passive"))
      (node (ref "RL3") (pin "8") (pinfunction "NO_8") (pintype "bidirectional"))
      (node (ref "RL3") (pin "9") (pinfunction "NO_9") (pintype "bidirectional"))
    )
    (net (code "91") (name "Net-(RL4B-NO)") (class "Default")
      (node (ref "C30") (pin "1") (pinfunction "1_1") (pintype "passive"))
      (node (ref "C31") (pin "1") (pinfunction "1_1") (pintype "passive"))
      (node (ref "L6") (pin "1") (pinfunction "1_1") (pintype "passive"))
      (node (ref "RL4") (pin "8") (pinfunction "NO_8") (pintype "bidirectional"))
      (node (ref "RL4") (pin "9") (pinfunction "NO_9") (pintype "bidirectional"))
    )
    (net (code "92") (name "Net-(T1-G)") (class "Default")
      (node (ref "R19") (pin "1") (pinfunction "1_1") (pintype "passive"))
      (node (ref "T1") (pin "4") (pinfunction "G_4") (pintype "passive"))
    )
    (net (code "93") (name "Net-(U1-RXI)") (class "Default")
      (node (ref "J10") (pin "2") (pinfunction "2_2") (pintype "passive"))
      (node (ref "U1") (pin "2") (pinfunction "RXI_2") (pintype "input"))
    )
    (net (code "94") (name "Net-(U1-TXO)") (class "Default")
      (node (ref "J10") (pin "4") (pinfunction "4_4") (pintype "passive"))
      (node (ref "U1") (pin "1") (pinfunction "TXO_1") (pintype "output"))
    )
    (net (code "95") (name "RPi_Vcc") (class "Default")
      (node (ref "C24") (pin "1") (pinfunction "1_1") (pintype "passive"))
      (node (ref "C25") (pin "1") (pinfunction "1_1") (pintype "passive"))
      (node (ref "C26") (pin "1") (pinfunction "1_1") (pintype "passive"))
      (node (ref "C27") (pin "1") (pinfunction "1_1") (pintype "passive"))
      (node (ref "L5") (pin "2") (pinfunction "2_2") (pintype "passive"))
      (node (ref "R12") (pin "1") (pinfunction "1_1") (pintype "passive"))
      (node (ref "RPI1") (pin "2") (pinfunction "+5V_2") (pintype "power_in"))
      (node (ref "RPI1") (pin "4") (pinfunction "+5V_4") (pintype "power_in"))
    )
    (net (code "96") (name "Srv_IO_Vcc") (class "Default")
      (node (ref "Q4") (pin "1") (pinfunction "G_1") (pintype "passive"))
      (node (ref "Q7") (pin "1") (pinfunction "G_1") (pintype "passive"))
      (node (ref "R1") (pin "1") (pinfunction "1_1") (pintype "passive"))
      (node (ref "R20") (pin "1") (pinfunction "1_1") (pintype "passive"))
      (node (ref "R27") (pin "1") (pinfunction "1_1") (pintype "passive"))
      (node (ref "R7") (pin "1") (pinfunction "1_1") (pintype "passive"))
      (node (ref "RPI1") (pin "17") (pinfunction "+3V3_17") (pintype "power_in"))
    )
    (net (code "97") (name "VCC_1") (class "Default")
      (node (ref "C14") (pin "1") (pinfunction "1_1") (pintype "passive"))
      (node (ref "C15") (pin "1") (pinfunction "1_1") (pintype "passive"))
      (node (ref "J16") (pin "1") (pinfunction "VBUS_1") (pintype "bidirectional"))
      (node (ref "L3") (pin "2") (pinfunction "2_2") (pintype "passive"))
      (node (ref "R16") (pin "1") (pinfunction "1_1") (pintype "passive"))
    )
    (net (code "98") (name "VCC_2") (class "Default")
      (node (ref "C32") (pin "1") (pinfunction "1_1") (pintype "passive"))
      (node (ref "C33") (pin "1") (pinfunction "1_1") (pintype "passive"))
      (node (ref "C34") (pin "1") (pinfunction "1_1") (pintype "passive"))
      (node (ref "J15") (pin "2") (pinfunction "2_2") (pintype "passive"))
      (node (ref "L6") (pin "2") (pinfunction "2_2") (pintype "passive"))
      (node (ref "R23") (pin "1") (pinfunction "1_1") (pintype "passive"))
      (node (ref "VC2") (pin "1") (pinfunction "Vcc_1") (pintype "power_in"))
    )
    (net (code "99") (name "VCC_KMA") (class "Default")
      (node (ref "C18") (pin "1") (pinfunction "1_1") (pintype "passive"))
      (node (ref "C19") (pin "1") (pinfunction "1_1") (pintype "passive"))
      (node (ref "J12") (pin "2") (pinfunction "2_2") (pintype "passive"))
      (node (ref "L4") (pin "2") (pinfunction "2_2") (pintype "passive"))
      (node (ref "R17") (pin "1") (pinfunction "1_1") (pintype "passive"))
      (node (ref "R21") (pin "1") (pinfunction "1_1") (pintype "passive"))
      (node (ref "R28") (pin "1") (pinfunction "1_1") (pintype "passive"))
      (node (ref "U1") (pin "21") (pinfunction "VCC_21") (pintype "power_in"))
    )
    (net (code "100") (name "unconnected-(B1-Pad1)") (class "Default")
      (node (ref "B1") (pin "1") (pinfunction "1_1") (pintype "power_in"))
    )
    (net (code "101") (name "unconnected-(B2-Pad1)") (class "Default")
      (node (ref "B2") (pin "1") (pinfunction "1_1") (pintype "power_in"))
    )
    (net (code "102") (name "unconnected-(B3-Pad1)") (class "Default")
      (node (ref "B3") (pin "1") (pinfunction "1_1") (pintype "power_in"))
    )
    (net (code "103") (name "unconnected-(B4-Pad1)") (class "Default")
      (node (ref "B4") (pin "1") (pinfunction "1_1") (pintype "power_in"))
    )
    (net (code "104") (name "unconnected-(B5-Pad1)") (class "Default")
      (node (ref "B5") (pin "1") (pinfunction "1_1") (pintype "power_in"))
    )
    (net (code "105") (name "unconnected-(B6-Pad1)") (class "Default")
      (node (ref "B6") (pin "1") (pinfunction "1_1") (pintype "power_in"))
    )
    (net (code "106") (name "unconnected-(B7-Pad1)") (class "Default")
      (node (ref "B7") (pin "1") (pinfunction "1_1") (pintype "power_in"))
    )
    (net (code "107") (name "unconnected-(B8-Pad1)") (class "Default")
      (node (ref "B8") (pin "1") (pinfunction "1_1") (pintype "power_in"))
    )
    (net (code "108") (name "unconnected-(J7-VBUS-Pad1)") (class "Default")
      (node (ref "J7") (pin "1") (pinfunction "VBUS_1") (pintype "bidirectional"))
    )
    (net (code "109") (name "unconnected-(J9-Pad2)") (class "Default")
      (node (ref "J9") (pin "2") (pinfunction "2_2") (pintype "power_in"))
    )
    (net (code "110") (name "unconnected-(J13-Pad1)") (class "Default")
      (node (ref "J13") (pin "1") (pinfunction "1_1") (pintype "passive"))
    )
    (net (code "111") (name "unconnected-(J13-Pad3)") (class "Default")
      (node (ref "J13") (pin "3") (pinfunction "3_3") (pintype "passive"))
    )
    (net (code "112") (name "unconnected-(J13-Pad5)") (class "Default")
      (node (ref "J13") (pin "5") (pinfunction "5_5") (pintype "passive"))
    )
    (net (code "113") (name "unconnected-(J13-Pad19)") (class "Default")
      (node (ref "J13") (pin "19") (pinfunction "19_19") (pintype "passive"))
    )
    (net (code "114") (name "unconnected-(J13-Pad20)") (class "Default")
      (node (ref "J13") (pin "20") (pinfunction "20_20") (pintype "passive"))
    )
    (net (code "115") (name "unconnected-(J13-Pad21)") (class "Default")
      (node (ref "J13") (pin "21") (pinfunction "21_21") (pintype "passive"))
    )
    (net (code "116") (name "unconnected-(J13-Pad22)") (class "Default")
      (node (ref "J13") (pin "22") (pinfunction "22_22") (pintype "passive"))
    )
    (net (code "117") (name "unconnected-(J13-Pad23)") (class "Default")
      (node (ref "J13") (pin "23") (pinfunction "23_23") (pintype "passive"))
    )
    (net (code "118") (name "unconnected-(J13-Pad24)") (class "Default")
      (node (ref "J13") (pin "24") (pinfunction "24_24") (pintype "passive"))
    )
    (net (code "119") (name "unconnected-(J13-Pad26)") (class "Default")
      (node (ref "J13") (pin "26") (pinfunction "26_26") (pintype "passive"))
    )
    (net (code "120") (name "unconnected-(J13-Pad27)") (class "Default")
      (node (ref "J13") (pin "27") (pinfunction "27_27") (pintype "passive"))
    )
    (net (code "121") (name "unconnected-(J13-Pad28)") (class "Default")
      (node (ref "J13") (pin "28") (pinfunction "28_28") (pintype "passive"))
    )
    (net (code "122") (name "unconnected-(J13-Pad29)") (class "Default")
      (node (ref "J13") (pin "29") (pinfunction "29_29") (pintype "passive"))
    )
    (net (code "123") (name "unconnected-(J13-Pad30)") (class "Default")
      (node (ref "J13") (pin "30") (pinfunction "30_30") (pintype "passive"))
    )
    (net (code "124") (name "unconnected-(J13-Pad31)") (class "Default")
      (node (ref "J13") (pin "31") (pinfunction "31_31") (pintype "passive"))
    )
    (net (code "125") (name "unconnected-(J13-Pad34)") (class "Default")
      (node (ref "J13") (pin "34") (pinfunction "34_34") (pintype "passive"))
    )
    (net (code "126") (name "unconnected-(J13-Pad35)") (class "Default")
      (node (ref "J13") (pin "35") (pinfunction "35_35") (pintype "passive"))
    )
    (net (code "127") (name "unconnected-(J13-Pad36)") (class "Default")
      (node (ref "J13") (pin "36") (pinfunction "36_36") (pintype "passive"))
    )
    (net (code "128") (name "unconnected-(J13-Pad38)") (class "Default")
      (node (ref "J13") (pin "38") (pinfunction "38_38") (pintype "passive"))
    )
    (net (code "129") (name "unconnected-(J13-Pad39)") (class "Default")
      (node (ref "J13") (pin "39") (pinfunction "39_39") (pintype "passive"))
    )
    (net (code "130") (name "unconnected-(J13-Pad40)") (class "Default")
      (node (ref "J13") (pin "40") (pinfunction "40_40") (pintype "passive"))
    )
    (net (code "131") (name "unconnected-(J14-Pad1)") (class "Default")
      (node (ref "J14") (pin "1") (pinfunction "1_1") (pintype "passive"))
    )
    (net (code "132") (name "unconnected-(J14-Pad3)") (class "Default")
      (node (ref "J14") (pin "3") (pinfunction "3_3") (pintype "passive"))
    )
    (net (code "133") (name "unconnected-(J14-Pad5)") (class "Default")
      (node (ref "J14") (pin "5") (pinfunction "5_5") (pintype "passive"))
    )
    (net (code "134") (name "unconnected-(J14-Pad19)") (class "Default")
      (node (ref "J14") (pin "19") (pinfunction "19_19") (pintype "passive"))
    )
    (net (code "135") (name "unconnected-(J14-Pad20)") (class "Default")
      (node (ref "J14") (pin "20") (pinfunction "20_20") (pintype "passive"))
    )
    (net (code "136") (name "unconnected-(J14-Pad21)") (class "Default")
      (node (ref "J14") (pin "21") (pinfunction "21_21") (pintype "passive"))
    )
    (net (code "137") (name "unconnected-(J14-Pad22)") (class "Default")
      (node (ref "J14") (pin "22") (pinfunction "22_22") (pintype "passive"))
    )
    (net (code "138") (name "unconnected-(J14-Pad23)") (class "Default")
      (node (ref "J14") (pin "23") (pinfunction "23_23") (pintype "passive"))
    )
    (net (code "139") (name "unconnected-(J14-Pad24)") (class "Default")
      (node (ref "J14") (pin "24") (pinfunction "24_24") (pintype "passive"))
    )
    (net (code "140") (name "unconnected-(J14-Pad26)") (class "Default")
      (node (ref "J14") (pin "26") (pinfunction "26_26") (pintype "passive"))
    )
    (net (code "141") (name "unconnected-(J14-Pad27)") (class "Default")
      (node (ref "J14") (pin "27") (pinfunction "27_27") (pintype "passive"))
    )
    (net (code "142") (name "unconnected-(J14-Pad28)") (class "Default")
      (node (ref "J14") (pin "28") (pinfunction "28_28") (pintype "passive"))
    )
    (net (code "143") (name "unconnected-(J14-Pad29)") (class "Default")
      (node (ref "J14") (pin "29") (pinfunction "29_29") (pintype "passive"))
    )
    (net (code "144") (name "unconnected-(J14-Pad30)") (class "Default")
      (node (ref "J14") (pin "30") (pinfunction "30_30") (pintype "passive"))
    )
    (net (code "145") (name "unconnected-(J14-Pad31)") (class "Default")
      (node (ref "J14") (pin "31") (pinfunction "31_31") (pintype "passive"))
    )
    (net (code "146") (name "unconnected-(J14-Pad34)") (class "Default")
      (node (ref "J14") (pin "34") (pinfunction "34_34") (pintype "passive"))
    )
    (net (code "147") (name "unconnected-(J14-Pad35)") (class "Default")
      (node (ref "J14") (pin "35") (pinfunction "35_35") (pintype "passive"))
    )
    (net (code "148") (name "unconnected-(J14-Pad36)") (class "Default")
      (node (ref "J14") (pin "36") (pinfunction "36_36") (pintype "passive"))
    )
    (net (code "149") (name "unconnected-(J14-Pad38)") (class "Default")
      (node (ref "J14") (pin "38") (pinfunction "38_38") (pintype "passive"))
    )
    (net (code "150") (name "unconnected-(J14-Pad39)") (class "Default")
      (node (ref "J14") (pin "39") (pinfunction "39_39") (pintype "passive"))
    )
    (net (code "151") (name "unconnected-(J14-Pad40)") (class "Default")
      (node (ref "J14") (pin "40") (pinfunction "40_40") (pintype "passive"))
    )
    (net (code "152") (name "unconnected-(RL1B-NO-Pad8)") (class "Default")
      (node (ref "RL1") (pin "8") (pinfunction "NO_8") (pintype "bidirectional"))
    )
    (net (code "153") (name "unconnected-(RL1C-NO-Pad9)") (class "Default")
      (node (ref "RL1") (pin "9") (pinfunction "NO_9") (pintype "bidirectional"))
    )
    (net (code "154") (name "unconnected-(RL3B-NC-Pad6)") (class "Default")
      (node (ref "RL3") (pin "6") (pinfunction "NC_6") (pintype "bidirectional"))
    )
    (net (code "155") (name "unconnected-(RL3C-NC-Pad11)") (class "Default")
      (node (ref "RL3") (pin "11") (pinfunction "NC_11") (pintype "bidirectional"))
    )
    (net (code "156") (name "unconnected-(RL4B-NC-Pad6)") (class "Default")
      (node (ref "RL4") (pin "6") (pinfunction "NC_6") (pintype "bidirectional"))
    )
    (net (code "157") (name "unconnected-(RL4C-NC-Pad11)") (class "Default")
      (node (ref "RL4") (pin "11") (pinfunction "NC_11") (pintype "bidirectional"))
    )
    (net (code "158") (name "unconnected-(RPI1-+3V3-Pad1)") (class "Default")
      (node (ref "RPI1") (pin "1") (pinfunction "+3V3_1") (pintype "power_in"))
    )
    (net (code "159") (name "unconnected-(RPI1-GND-Pad20)") (class "Default")
      (node (ref "RPI1") (pin "20") (pinfunction "GND_20") (pintype "power_in"))
    )
    (net (code "160") (name "unconnected-(RPI1-GND-Pad30)") (class "Default")
      (node (ref "RPI1") (pin "30") (pinfunction "GND_30") (pintype "power_in"))
    )
    (net (code "161") (name "unconnected-(RPI1-GND-Pad34)") (class "Default")
      (node (ref "RPI1") (pin "34") (pinfunction "GND_34") (pintype "passive"))
    )
    (net (code "162") (name "unconnected-(RPI1-GND-Pad39)") (class "Default")
      (node (ref "RPI1") (pin "39") (pinfunction "GND_39") (pintype "power_in"))
    )
    (net (code "163") (name "unconnected-(RPI1-GPIO2_(I2C_SDA)-Pad3)") (class "Default")
      (node (ref "RPI1") (pin "3") (pinfunction "GPIO2_(I2C_SDA)_3") (pintype "bidirectional"))
    )
    (net (code "164") (name "unconnected-(RPI1-GPIO3_(I2C_SCL)-Pad5)") (class "Default")
      (node (ref "RPI1") (pin "5") (pinfunction "GPIO3_(I2C_SCL)_5") (pintype "bidirectional"))
    )
    (net (code "165") (name "unconnected-(RPI1-GPIO5-Pad29)") (class "Default")
      (node (ref "RPI1") (pin "29") (pinfunction "GPIO5_29") (pintype "bidirectional"))
    )
    (net (code "166") (name "unconnected-(RPI1-GPIO6-Pad31)") (class "Default")
      (node (ref "RPI1") (pin "31") (pinfunction "GPIO6_31") (pintype "bidirectional"))
    )
    (net (code "167") (name "unconnected-(RPI1-GPIO7_(SPI0_CS1)-Pad26)") (class "Default")
      (node (ref "RPI1") (pin "26") (pinfunction "GPIO7_(SPI0_CS1)_26") (pintype "bidirectional"))
    )
    (net (code "168") (name "unconnected-(RPI1-GPIO8_(SPI0_CS0)-Pad24)") (class "Default")
      (node (ref "RPI1") (pin "24") (pinfunction "GPIO8_(SPI0_CS0)_24") (pintype "bidirectional"))
    )
    (net (code "169") (name "unconnected-(RPI1-GPIO9_(SPI0_MISO)-Pad21)") (class "Default")
      (node (ref "RPI1") (pin "21") (pinfunction "GPIO9_(SPI0_MISO)_21") (pintype "bidirectional"))
    )
    (net (code "170") (name "unconnected-(RPI1-GPIO10_(SPI0_MOSI)-Pad19)") (class "Default")
      (node (ref "RPI1") (pin "19") (pinfunction "GPIO10_(SPI0_MOSI)_19") (pintype "bidirectional"))
    )
    (net (code "171") (name "unconnected-(RPI1-GPIO11_(SPI0_SCLK)-Pad23)") (class "Default")
      (node (ref "RPI1") (pin "23") (pinfunction "GPIO11_(SPI0_SCLK)_23") (pintype "bidirectional"))
    )
    (net (code "172") (name "unconnected-(RPI1-GPIO16_(SPI1_CS0)-Pad36)") (class "Default")
      (node (ref "RPI1") (pin "36") (pinfunction "GPIO16_(SPI1_CS0)_36") (pintype "bidirectional"))
    )
    (net (code "173") (name "unconnected-(RPI1-GPIO19_(SPI1_MISO)-Pad35)") (class "Default")
      (node (ref "RPI1") (pin "35") (pinfunction "GPIO19_(SPI1_MISO)_35") (pintype "bidirectional"))
    )
    (net (code "174") (name "unconnected-(RPI1-GPIO20_(SPI1_MOSI)-Pad38)") (class "Default")
      (node (ref "RPI1") (pin "38") (pinfunction "GPIO20_(SPI1_MOSI)_38") (pintype "bidirectional"))
    )
    (net (code "175") (name "unconnected-(RPI1-GPIO21_(SPI1_SCLK)-Pad40)") (class "Default")
      (node (ref "RPI1") (pin "40") (pinfunction "GPIO21_(SPI1_SCLK)_40") (pintype "bidirectional"))
    )
    (net (code "176") (name "unconnected-(RPI1-GPIO25-Pad22)") (class "Default")
      (node (ref "RPI1") (pin "22") (pinfunction "GPIO25_22") (pintype "bidirectional"))
    )
    (net (code "177") (name "unconnected-(RPI1-RSVD-Pad27)") (class "Default")
      (node (ref "RPI1") (pin "27") (pinfunction "RSVD_27") (pintype "passive"))
    )
    (net (code "178") (name "unconnected-(RPI1-RSVD-Pad28)") (class "Default")
      (node (ref "RPI1") (pin "28") (pinfunction "RSVD_28") (pintype "passive"))
    )
    (net (code "179") (name "unconnected-(U1-2-Pad5)") (class "Default")
      (node (ref "U1") (pin "5") (pinfunction "2_5") (pintype "bidirectional"))
    )
    (net (code "180") (name "unconnected-(U1-3-Pad6)") (class "Default")
      (node (ref "U1") (pin "6") (pinfunction "3_6") (pintype "bidirectional"))
    )
    (net (code "181") (name "unconnected-(U1-4-Pad7)") (class "Default")
      (node (ref "U1") (pin "7") (pinfunction "4_7") (pintype "bidirectional"))
    )
    (net (code "182") (name "unconnected-(U1-5-Pad8)") (class "Default")
      (node (ref "U1") (pin "8") (pinfunction "5_8") (pintype "bidirectional"))
    )
    (net (code "183") (name "unconnected-(U1-6-Pad9)") (class "Default")
      (node (ref "U1") (pin "9") (pinfunction "6_9") (pintype "bidirectional"))
    )
    (net (code "184") (name "unconnected-(U1-7-Pad10)") (class "Default")
      (node (ref "U1") (pin "10") (pinfunction "7_10") (pintype "bidirectional"))
    )
    (net (code "185") (name "unconnected-(U1-8-Pad11)") (class "Default")
      (node (ref "U1") (pin "11") (pinfunction "8_11") (pintype "bidirectional"))
    )
    (net (code "186") (name "unconnected-(U1-9-Pad12)") (class "Default")
      (node (ref "U1") (pin "12") (pinfunction "9_12") (pintype "bidirectional"))
    )
    (net (code "187") (name "unconnected-(U1-10-Pad13)") (class "Default")
      (node (ref "U1") (pin "13") (pinfunction "10_13") (pintype "bidirectional"))
    )
    (net (code "188") (name "unconnected-(U1-A0-Pad17)") (class "Default")
      (node (ref "U1") (pin "17") (pinfunction "A0_17") (pintype "bidirectional"))
    )
    (net (code "189") (name "unconnected-(U1-A1-Pad18)") (class "Default")
      (node (ref "U1") (pin "18") (pinfunction "A1_18") (pintype "bidirectional"))
    )
    (net (code "190") (name "unconnected-(U1-A2-Pad19)") (class "Default")
      (node (ref "U1") (pin "19") (pinfunction "A2_19") (pintype "bidirectional"))
    )
    (net (code "191") (name "unconnected-(U1-A3-Pad20)") (class "Default")
      (node (ref "U1") (pin "20") (pinfunction "A3_20") (pintype "bidirectional"))
    )
    (net (code "192") (name "unconnected-(U1-RAW-Pad24)") (class "Default")
      (node (ref "U1") (pin "24") (pinfunction "RAW_24") (pintype "power_in"))
    )
    (net (code "193") (name "unconnected-(VC1-Pad0)") (class "Default")
      (node (ref "VC1") (pin "0") (pinfunction "0_0") (pintype "passive"))
    )
  )
)
